# M_2_SoM_breakout_board_v0_4.net
KiCad netlist of a schematic drawn in EAGLE
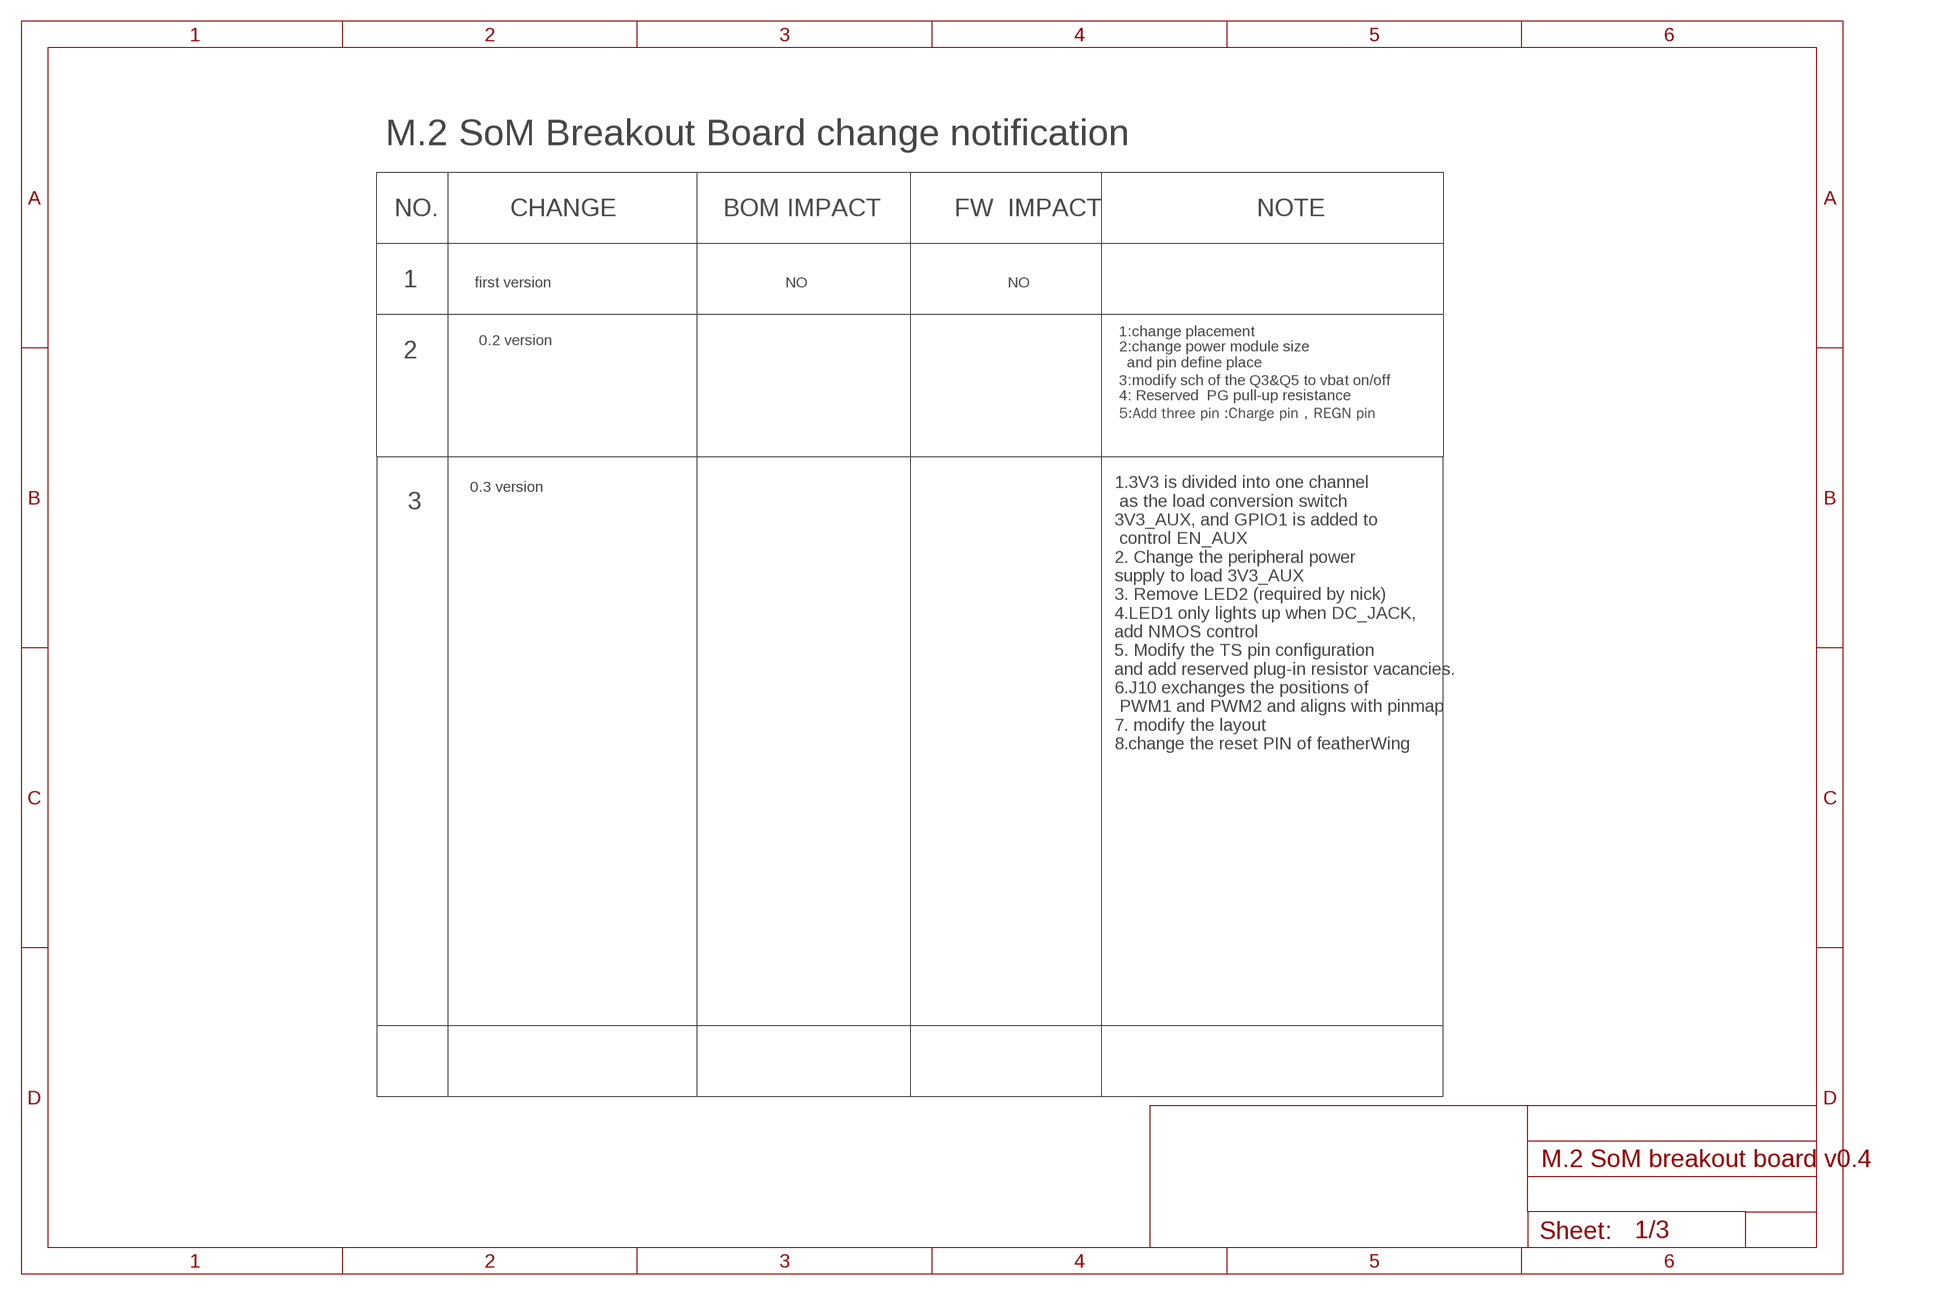
[diagram p0: schematic, sheet 1]
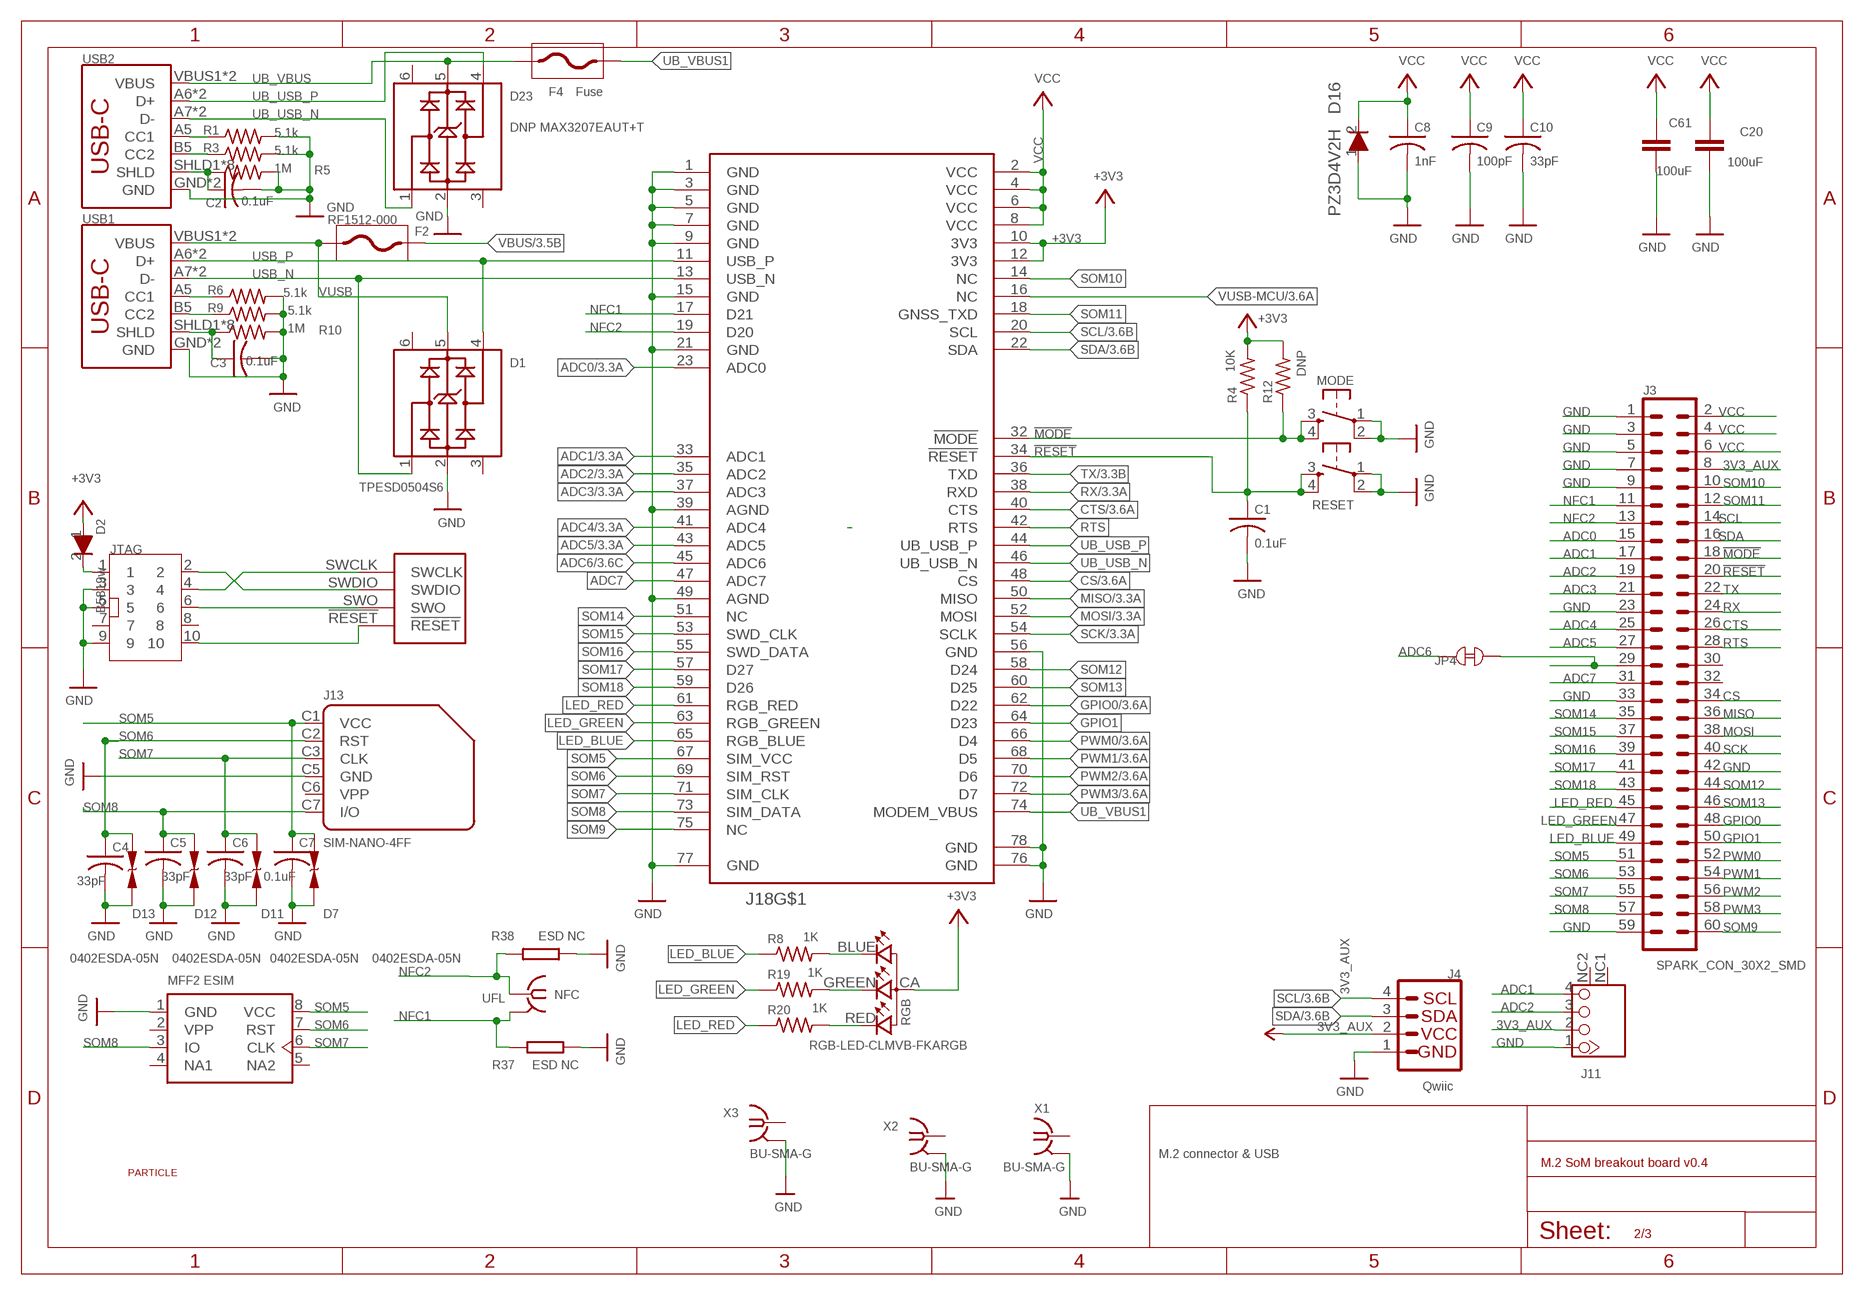
[diagram p1: schematic, sheet 2]
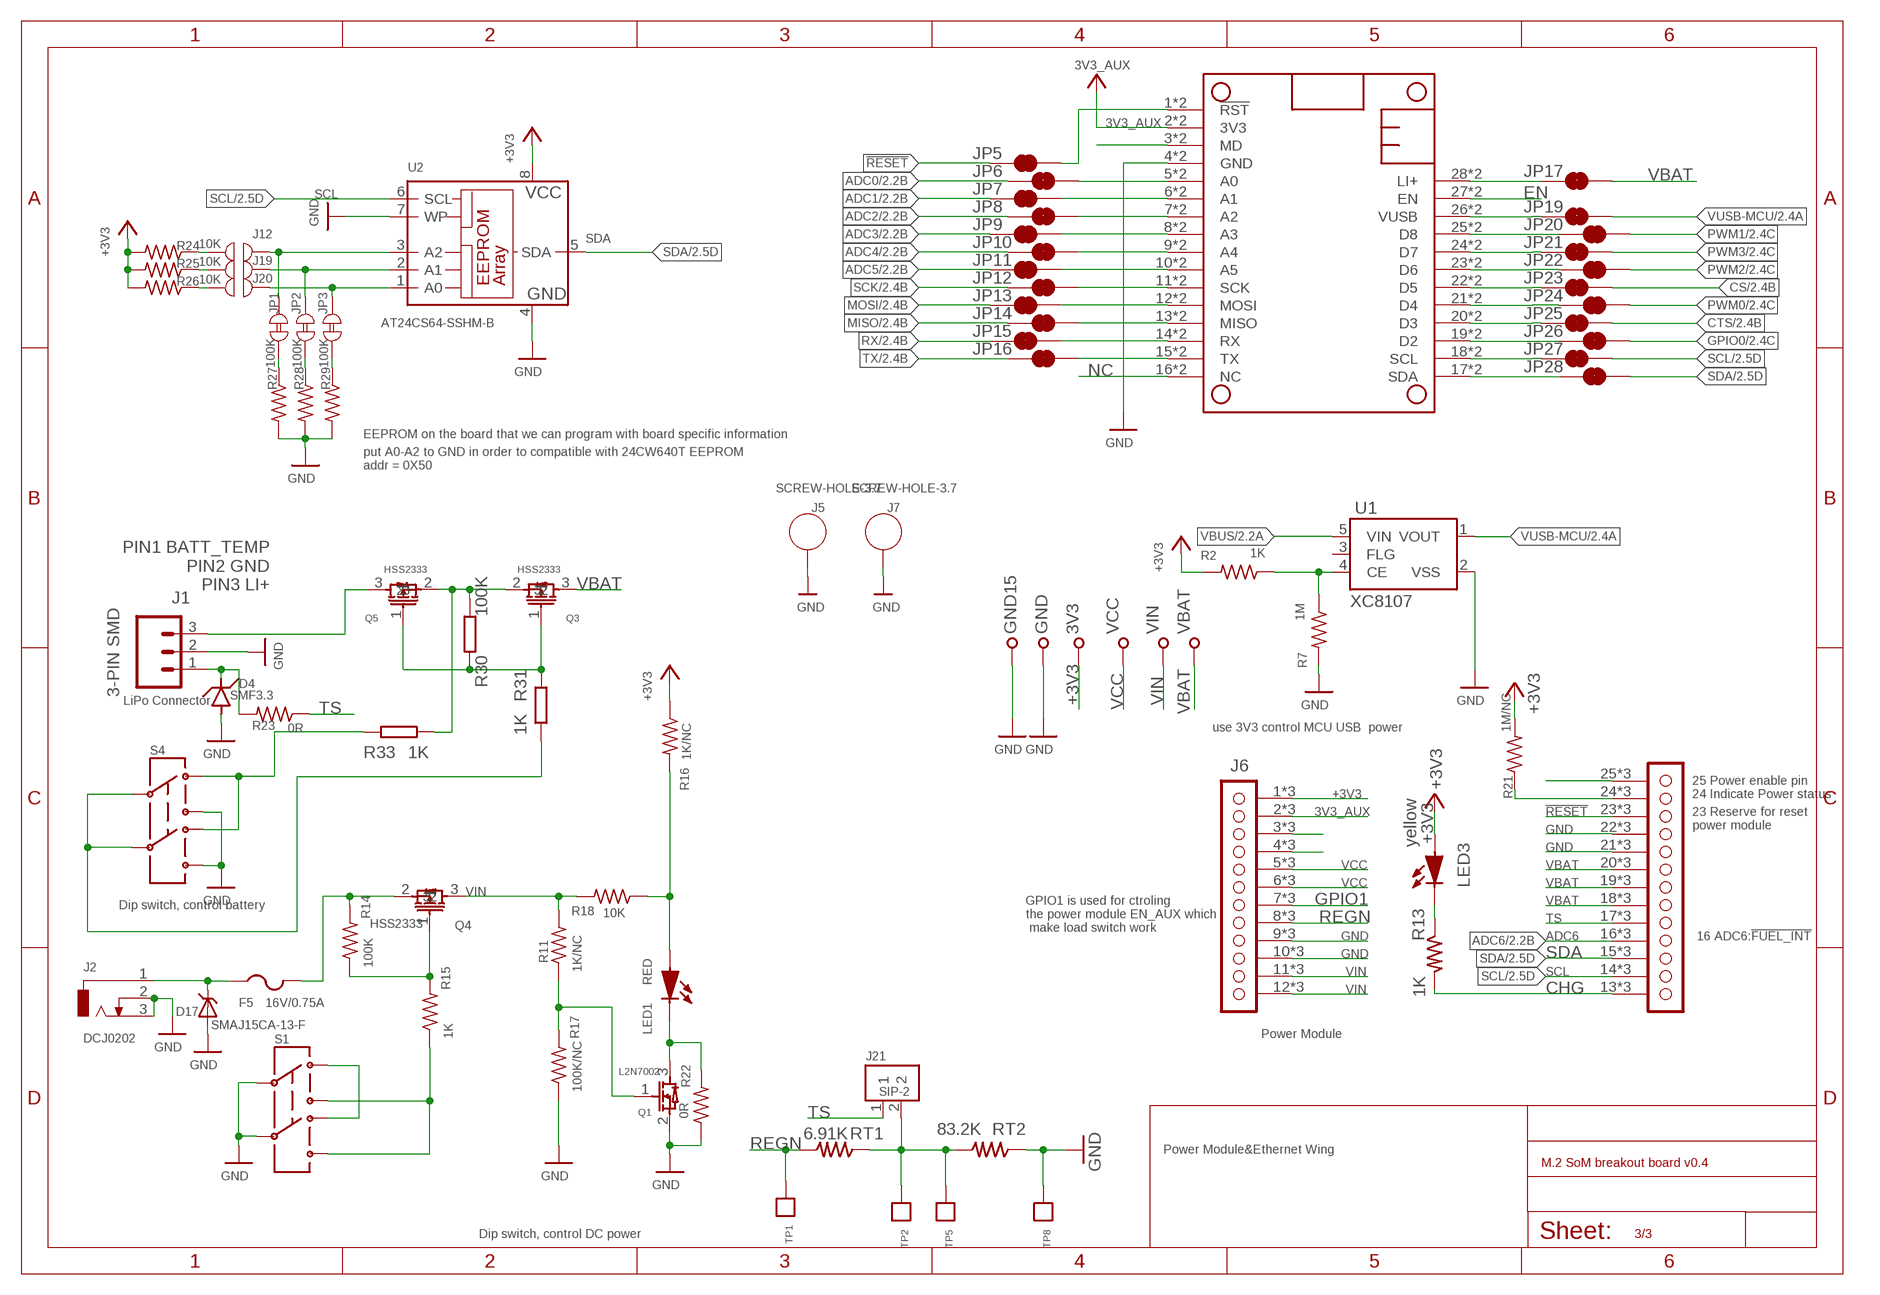
[diagram p2: schematic, sheet 3]

(export (version "E")
  (design (tool "Eeschema 10.0.6"))
  (components
    (comp (ref "3V3")
      (value "TP-S2751-46R")
      (footprint "eagle-import:S2751-46R")
      (libsource (lib "eagle-import") (part "TP-S2751-46R"))
    )
    (comp (ref "D4")
      (value "SMF3.3")
      (footprint "eagle-import:SOD-123FL")
      (libsource (lib "eagle-import") (part "TVS-DIODE-SOD123FL"))
    )
    (comp (ref "D17")
      (value "SMAJ15CA-13-F")
      (footprint "eagle-import:SMADIODE")
      (libsource (lib "eagle-import") (part "DIODE-ZENER"))
    )
    (comp (ref "F5")
      (value "16V/0.75A")
      (footprint "eagle-import:1812")
      (libsource (lib "eagle-import") (part "PTCFUSE-1812"))
    )
    (comp (ref "GND")
      (value "TP-S2751-46R")
      (footprint "eagle-import:S2751-46R")
      (libsource (lib "eagle-import") (part "TP-S2751-46R"))
    )
    (comp (ref "GND15")
      (value "TP-S2751-46R")
      (footprint "eagle-import:S2751-46R")
      (libsource (lib "eagle-import") (part "TP-S2751-46R"))
    )
    (comp (ref "J1")
      (value "3-PIN SMD")
      (footprint "eagle-import:JST-3-SMD")
      (libsource (lib "eagle-import") (part "CONN_03JST-SMD"))
    )
    (comp (ref "J2")
      (value "DCJ0202")
      (footprint "eagle-import:DCJ0202")
      (libsource (lib "eagle-import") (part "DCJ0202"))
    )
    (comp (ref "J5")
      (value "SCREW-HOLE-3.7")
      (footprint "eagle-import:SCREW-HOLE-3.7")
      (libsource (lib "eagle-import") (part "SCREW-HOLE-3.7"))
    )
    (comp (ref "J6")
      (value "M.2-SOM-BREAKOUT-BOARD-V0.2-0228_PARTICLE-SZ_PARTICLE-POWER-MODULE")
      (footprint "eagle-import:M.2-SOM-BREAKOUT-BOARD-V0.2-0228_PARTICLE-SZ_PARTICLE-POWER-MODULE")
      (libsource (lib "eagle-import") (part "M.2-SOM-BREAKOUT-BOARD-V0.2-0228_PARTICLE-SZ_PARTICLE-POWER-MODULE"))
    )
    (comp (ref "J7")
      (value "SCREW-HOLE-3.7")
      (footprint "eagle-import:SCREW-HOLE-3.7")
      (libsource (lib "eagle-import") (part "SCREW-HOLE-3.7"))
    )
    (comp (ref "J12")
      (value "TP_OPEN")
      (footprint "eagle-import:TP_OPEN")
      (libsource (lib "eagle-import") (part "TP_OPEN"))
    )
    (comp (ref "J19")
      (value "TP_OPEN")
      (footprint "eagle-import:TP_OPEN")
      (libsource (lib "eagle-import") (part "TP_OPEN"))
    )
    (comp (ref "J20")
      (value "TP_OPEN")
      (footprint "eagle-import:TP_OPEN")
      (libsource (lib "eagle-import") (part "TP_OPEN"))
    )
    (comp (ref "J21")
      (value "SIP-2")
      (footprint "eagle-import:SIP-2")
      (libsource (lib "eagle-import") (part "SIP-2"))
    )
    (comp (ref "JP1")
      (value "TP_SHORT")
      (footprint "eagle-import:TP_SHORT")
      (libsource (lib "eagle-import") (part "TP_SHORT"))
    )
    (comp (ref "JP2")
      (value "TP_SHORT")
      (footprint "eagle-import:TP_SHORT")
      (libsource (lib "eagle-import") (part "TP_SHORT"))
    )
    (comp (ref "JP3")
      (value "TP_SHORT")
      (footprint "eagle-import:TP_SHORT")
      (libsource (lib "eagle-import") (part "TP_SHORT"))
    )
    (comp (ref "JP5")
      (value "JUMPER-SMT_2_NC_TRACE_NO-SILK")
      (footprint "eagle-import:SMT-JUMPER_2_NC_TRACE_NO-SILK")
      (libsource (lib "eagle-import") (part "JUMPER-SMT_2_NC_TRACE_NO-SILK"))
    )
    (comp (ref "JP6")
      (value "JUMPER-SMT_2_NC_TRACE_NO-SILK")
      (footprint "eagle-import:SMT-JUMPER_2_NC_TRACE_NO-SILK")
      (libsource (lib "eagle-import") (part "JUMPER-SMT_2_NC_TRACE_NO-SILK"))
    )
    (comp (ref "JP7")
      (value "JUMPER-SMT_2_NC_TRACE_NO-SILK")
      (footprint "eagle-import:SMT-JUMPER_2_NC_TRACE_NO-SILK")
      (libsource (lib "eagle-import") (part "JUMPER-SMT_2_NC_TRACE_NO-SILK"))
    )
    (comp (ref "JP8")
      (value "JUMPER-SMT_2_NC_TRACE_NO-SILK")
      (footprint "eagle-import:SMT-JUMPER_2_NC_TRACE_NO-SILK")
      (libsource (lib "eagle-import") (part "JUMPER-SMT_2_NC_TRACE_NO-SILK"))
    )
    (comp (ref "JP9")
      (value "JUMPER-SMT_2_NC_TRACE_NO-SILK")
      (footprint "eagle-import:SMT-JUMPER_2_NC_TRACE_NO-SILK")
      (libsource (lib "eagle-import") (part "JUMPER-SMT_2_NC_TRACE_NO-SILK"))
    )
    (comp (ref "JP10")
      (value "JUMPER-SMT_2_NC_TRACE_NO-SILK")
      (footprint "eagle-import:SMT-JUMPER_2_NC_TRACE_NO-SILK")
      (libsource (lib "eagle-import") (part "JUMPER-SMT_2_NC_TRACE_NO-SILK"))
    )
    (comp (ref "JP11")
      (value "JUMPER-SMT_2_NC_TRACE_NO-SILK")
      (footprint "eagle-import:SMT-JUMPER_2_NC_TRACE_NO-SILK")
      (libsource (lib "eagle-import") (part "JUMPER-SMT_2_NC_TRACE_NO-SILK"))
    )
    (comp (ref "JP12")
      (value "JUMPER-SMT_2_NC_TRACE_NO-SILK")
      (footprint "eagle-import:SMT-JUMPER_2_NC_TRACE_NO-SILK")
      (libsource (lib "eagle-import") (part "JUMPER-SMT_2_NC_TRACE_NO-SILK"))
    )
    (comp (ref "JP13")
      (value "JUMPER-SMT_2_NC_TRACE_NO-SILK")
      (footprint "eagle-import:SMT-JUMPER_2_NC_TRACE_NO-SILK")
      (libsource (lib "eagle-import") (part "JUMPER-SMT_2_NC_TRACE_NO-SILK"))
    )
    (comp (ref "JP14")
      (value "JUMPER-SMT_2_NC_TRACE_NO-SILK")
      (footprint "eagle-import:SMT-JUMPER_2_NC_TRACE_NO-SILK")
      (libsource (lib "eagle-import") (part "JUMPER-SMT_2_NC_TRACE_NO-SILK"))
    )
    (comp (ref "JP15")
      (value "JUMPER-SMT_2_NC_TRACE_NO-SILK")
      (footprint "eagle-import:SMT-JUMPER_2_NC_TRACE_NO-SILK")
      (libsource (lib "eagle-import") (part "JUMPER-SMT_2_NC_TRACE_NO-SILK"))
    )
    (comp (ref "JP16")
      (value "JUMPER-SMT_2_NC_TRACE_NO-SILK")
      (footprint "eagle-import:SMT-JUMPER_2_NC_TRACE_NO-SILK")
      (libsource (lib "eagle-import") (part "JUMPER-SMT_2_NC_TRACE_NO-SILK"))
    )
    (comp (ref "JP17")
      (value "JUMPER-SMT_2_NC_TRACE_NO-SILK")
      (footprint "eagle-import:SMT-JUMPER_2_NC_TRACE_NO-SILK")
      (libsource (lib "eagle-import") (part "JUMPER-SMT_2_NC_TRACE_NO-SILK"))
    )
    (comp (ref "JP19")
      (value "JUMPER-SMT_2_NC_TRACE_NO-SILK")
      (footprint "eagle-import:SMT-JUMPER_2_NC_TRACE_NO-SILK")
      (libsource (lib "eagle-import") (part "JUMPER-SMT_2_NC_TRACE_NO-SILK"))
    )
    (comp (ref "JP20")
      (value "JUMPER-SMT_2_NC_TRACE_NO-SILK")
      (footprint "eagle-import:SMT-JUMPER_2_NC_TRACE_NO-SILK")
      (libsource (lib "eagle-import") (part "JUMPER-SMT_2_NC_TRACE_NO-SILK"))
    )
    (comp (ref "JP21")
      (value "JUMPER-SMT_2_NC_TRACE_NO-SILK")
      (footprint "eagle-import:SMT-JUMPER_2_NC_TRACE_NO-SILK")
      (libsource (lib "eagle-import") (part "JUMPER-SMT_2_NC_TRACE_NO-SILK"))
    )
    (comp (ref "JP22")
      (value "JUMPER-SMT_2_NC_TRACE_NO-SILK")
      (footprint "eagle-import:SMT-JUMPER_2_NC_TRACE_NO-SILK")
      (libsource (lib "eagle-import") (part "JUMPER-SMT_2_NC_TRACE_NO-SILK"))
    )
    (comp (ref "JP23")
      (value "JUMPER-SMT_2_NC_TRACE_NO-SILK")
      (footprint "eagle-import:SMT-JUMPER_2_NC_TRACE_NO-SILK")
      (libsource (lib "eagle-import") (part "JUMPER-SMT_2_NC_TRACE_NO-SILK"))
    )
    (comp (ref "JP24")
      (value "JUMPER-SMT_2_NC_TRACE_NO-SILK")
      (footprint "eagle-import:SMT-JUMPER_2_NC_TRACE_NO-SILK")
      (libsource (lib "eagle-import") (part "JUMPER-SMT_2_NC_TRACE_NO-SILK"))
    )
    (comp (ref "JP25")
      (value "JUMPER-SMT_2_NC_TRACE_NO-SILK")
      (footprint "eagle-import:SMT-JUMPER_2_NC_TRACE_NO-SILK")
      (libsource (lib "eagle-import") (part "JUMPER-SMT_2_NC_TRACE_NO-SILK"))
    )
    (comp (ref "JP26")
      (value "JUMPER-SMT_2_NC_TRACE_NO-SILK")
      (footprint "eagle-import:SMT-JUMPER_2_NC_TRACE_NO-SILK")
      (libsource (lib "eagle-import") (part "JUMPER-SMT_2_NC_TRACE_NO-SILK"))
    )
    (comp (ref "JP27")
      (value "JUMPER-SMT_2_NC_TRACE_NO-SILK")
      (footprint "eagle-import:SMT-JUMPER_2_NC_TRACE_NO-SILK")
      (libsource (lib "eagle-import") (part "JUMPER-SMT_2_NC_TRACE_NO-SILK"))
    )
    (comp (ref "JP28")
      (value "JUMPER-SMT_2_NC_TRACE_NO-SILK")
      (footprint "eagle-import:SMT-JUMPER_2_NC_TRACE_NO-SILK")
      (libsource (lib "eagle-import") (part "JUMPER-SMT_2_NC_TRACE_NO-SILK"))
    )
    (comp (ref "LED1")
      (value "RED")
      (footprint "eagle-import:LED0603")
      (libsource (lib "eagle-import") (part "LED"))
    )
    (comp (ref "LED3")
      (value "yellow")
      (footprint "eagle-import:LED0603")
      (libsource (lib "eagle-import") (part "LED"))
    )
    (comp (ref "MS1")
      (value "PARTICLE_MESH_SMTDUAL")
      (footprint "eagle-import:FEATHERWING_SMT2")
      (libsource (lib "eagle-import") (part "PARTICLE_MESH_SMTDUAL"))
    )
    (comp (ref "Q1")
      (value "L2N7002")
      (footprint "eagle-import:SOT323")
      (libsource (lib "eagle-import") (part "NMOSSOT323"))
    )
    (comp (ref "Q3")
      (value "HSS2333")
      (footprint "eagle-import:SOT-23")
      (libsource (lib "eagle-import") (part "PMOS"))
    )
    (comp (ref "Q4")
      (value "HSS2333")
      (footprint "eagle-import:SOT-23")
      (libsource (lib "eagle-import") (part "PMOS"))
    )
    (comp (ref "Q5")
      (value "HSS2333")
      (footprint "eagle-import:SOT-23")
      (libsource (lib "eagle-import") (part "PMOS"))
    )
    (comp (ref "R2")
      (value "1K")
      (footprint "eagle-import:R0402_B")
      (libsource (lib "eagle-import") (part "R-US_"))
    )
    (comp (ref "R7")
      (value "1M")
      (footprint "eagle-import:R0402_B")
      (libsource (lib "eagle-import") (part "R-US_"))
    )
    (comp (ref "R11")
      (value "1K/NC")
      (footprint "eagle-import:R0402_B")
      (libsource (lib "eagle-import") (part "R-US_"))
    )
    (comp (ref "R13")
      (value "1K")
      (footprint "eagle-import:R-0402S")
      (libsource (lib "eagle-import") (part "particle SZ_RES0402S"))
    )
    (comp (ref "R14")
      (value "100K")
      (footprint "eagle-import:R0402_B")
      (libsource (lib "eagle-import") (part "R-US_"))
    )
    (comp (ref "R15")
      (value "1K")
      (footprint "eagle-import:R0402_B")
      (libsource (lib "eagle-import") (part "R-US_"))
    )
    (comp (ref "R16")
      (value "1K/NC")
      (footprint "eagle-import:R0402_B")
      (libsource (lib "eagle-import") (part "R-US_"))
    )
    (comp (ref "R17")
      (value "100K/NC")
      (footprint "eagle-import:R0402_B")
      (libsource (lib "eagle-import") (part "R-US_"))
    )
    (comp (ref "R18")
      (value "10K")
      (footprint "eagle-import:R0402_B")
      (libsource (lib "eagle-import") (part "R-US_"))
    )
    (comp (ref "R21")
      (value "1M/NC")
      (footprint "eagle-import:R0402_B")
      (libsource (lib "eagle-import") (part "R-US_"))
    )
    (comp (ref "R22")
      (value "0R")
      (footprint "eagle-import:R0402_B")
      (libsource (lib "eagle-import") (part "R-US_"))
    )
    (comp (ref "R23")
      (value "0R")
      (footprint "eagle-import:R0402_B")
      (libsource (lib "eagle-import") (part "R-US_"))
    )
    (comp (ref "R24")
      (value "10K")
      (footprint "eagle-import:R0402_B")
      (libsource (lib "eagle-import") (part "R-US_"))
    )
    (comp (ref "R25")
      (value "10K")
      (footprint "eagle-import:R0402_B")
      (libsource (lib "eagle-import") (part "R-US_"))
    )
    (comp (ref "R26")
      (value "10K")
      (footprint "eagle-import:R0402_B")
      (libsource (lib "eagle-import") (part "R-US_"))
    )
    (comp (ref "R27")
      (value "100K")
      (footprint "eagle-import:R0402_B")
      (libsource (lib "eagle-import") (part "R-US_"))
    )
    (comp (ref "R28")
      (value "100K")
      (footprint "eagle-import:R0402_B")
      (libsource (lib "eagle-import") (part "R-US_"))
    )
    (comp (ref "R29")
      (value "100K")
      (footprint "eagle-import:R0402_B")
      (libsource (lib "eagle-import") (part "R-US_"))
    )
    (comp (ref "R30")
      (value "100K")
      (footprint "eagle-import:R0603")
      (libsource (lib "eagle-import") (part "RESR0603"))
    )
    (comp (ref "R31")
      (value "1K")
      (footprint "eagle-import:R-0402S")
      (libsource (lib "eagle-import") (part "RES0402S"))
    )
    (comp (ref "R33")
      (value "1K")
      (footprint "eagle-import:R-0402S")
      (libsource (lib "eagle-import") (part "RES0402S"))
    )
    (comp (ref "RT1")
      (value "6.91K")
      (footprint "eagle-import:R-0603A")
      (libsource (lib "eagle-import") (part "RESR0603A"))
    )
    (comp (ref "RT2")
      (value "83.2K")
      (footprint "eagle-import:R-0603A")
      (libsource (lib "eagle-import") (part "RESR0603A"))
    )
    (comp (ref "S1")
      (value "SWITCH-DPDT")
      (footprint "eagle-import:SWITCH-2.5X3.2-6")
      (libsource (lib "eagle-import") (part "SWITCH-DPDT"))
    )
    (comp (ref "S4")
      (value "SWITCH-DPDT")
      (footprint "eagle-import:SWITCH-2.5X3.2-6")
      (libsource (lib "eagle-import") (part "SWITCH-DPDT"))
    )
    (comp (ref "TP1")
      (value "TPTPEB")
      (footprint "eagle-import:TPEB")
      (libsource (lib "eagle-import") (part "TPTPEB"))
    )
    (comp (ref "TP2")
      (value "TPTPEB")
      (footprint "eagle-import:TPEB")
      (libsource (lib "eagle-import") (part "TPTPEB"))
    )
    (comp (ref "TP5")
      (value "TPTPEB")
      (footprint "eagle-import:TPEB")
      (libsource (lib "eagle-import") (part "TPTPEB"))
    )
    (comp (ref "TP8")
      (value "TPTPEB")
      (footprint "eagle-import:TPEB")
      (libsource (lib "eagle-import") (part "TPTPEB"))
    )
    (comp (ref "U1")
      (value "XC8107")
      (footprint "eagle-import:SOT25")
      (libsource (lib "eagle-import") (part "XC8107SOT25"))
    )
    (comp (ref "U2")
      (value "AT24CS64-SSHM-B")
      (footprint "eagle-import:SO-08")
      (fields (field (name "MF") "MICROCHIP") (field (name "MPN") "24AA01/SN"))
      (libsource (lib "eagle-import") (part "24SNAA01"))
    )
    (comp (ref "VBAT")
      (value "TP-S2751-46R")
      (footprint "eagle-import:S2751-46R")
      (libsource (lib "eagle-import") (part "TP-S2751-46R"))
    )
    (comp (ref "VCC")
      (value "TP-S2751-46R")
      (footprint "eagle-import:S2751-46R")
      (libsource (lib "eagle-import") (part "TP-S2751-46R"))
    )
    (comp (ref "VIN")
      (value "TP-S2751-46R")
      (footprint "eagle-import:S2751-46R")
      (libsource (lib "eagle-import") (part "TP-S2751-46R"))
    )
    (comp (ref "C1")
      (value "0.1uF")
      (footprint "eagle-import:C0402_B")
      (libsource (lib "eagle-import") (part "C-US"))
    )
    (comp (ref "C2")
      (value "0.1uF")
      (footprint "eagle-import:C0402_B")
      (libsource (lib "eagle-import") (part "C-US"))
    )
    (comp (ref "C3")
      (value "0.1uF")
      (footprint "eagle-import:C0402_B")
      (libsource (lib "eagle-import") (part "C-US"))
    )
    (comp (ref "C4")
      (value "33pF")
      (footprint "eagle-import:C0402_B")
      (libsource (lib "eagle-import") (part "C-US"))
    )
    (comp (ref "C5")
      (value "33pF")
      (footprint "eagle-import:C0402_B")
      (libsource (lib "eagle-import") (part "C-US"))
    )
    (comp (ref "C6")
      (value "33pF")
      (footprint "eagle-import:C0402_B")
      (libsource (lib "eagle-import") (part "C-US"))
    )
    (comp (ref "C7")
      (value "0.1uF")
      (footprint "eagle-import:C0402_B")
      (libsource (lib "eagle-import") (part "C-US"))
    )
    (comp (ref "C8")
      (value "1nF")
      (footprint "eagle-import:C0402_B")
      (libsource (lib "eagle-import") (part "C-US"))
    )
    (comp (ref "C9")
      (value "100pF")
      (footprint "eagle-import:C0402_B")
      (libsource (lib "eagle-import") (part "C-US"))
    )
    (comp (ref "C10")
      (value "33pF")
      (footprint "eagle-import:C0402_B")
      (libsource (lib "eagle-import") (part "C-US"))
    )
    (comp (ref "C20")
      (value "100uF")
      (footprint "eagle-import:C1206K")
      (libsource (lib "eagle-import") (part "C-EUC1206K"))
    )
    (comp (ref "C61")
      (value "100uF")
      (footprint "eagle-import:C1206K")
      (libsource (lib "eagle-import") (part "C-EUC1206K"))
    )
    (comp (ref "D1")
      (value "TPESD0504S6")
      (footprint "eagle-import:SOT23-6")
      (fields (field (name "MFG") "MAXIM") (field (name "MPN") "MAX3207EAUT+T"))
      (libsource (lib "eagle-import") (part "MAX3207EAUT+T"))
    )
    (comp (ref "D2")
      (value "B5819w")
      (footprint "eagle-import:SOD-123")
      (libsource (lib "eagle-import") (part "DIODESOD123"))
    )
    (comp (ref "D7")
      (value "0402ESDA-05N")
      (footprint "eagle-import:C0402")
      (libsource (lib "eagle-import") (part "ESD"))
    )
    (comp (ref "D11")
      (value "0402ESDA-05N")
      (footprint "eagle-import:C0402")
      (libsource (lib "eagle-import") (part "ESD"))
    )
    (comp (ref "D12")
      (value "0402ESDA-05N")
      (footprint "eagle-import:C0402")
      (libsource (lib "eagle-import") (part "ESD"))
    )
    (comp (ref "D13")
      (value "0402ESDA-05N")
      (footprint "eagle-import:C0402")
      (libsource (lib "eagle-import") (part "ESD"))
    )
    (comp (ref "D16")
      (value "PZ3D4V2H")
      (footprint "eagle-import:SOD-323")
      (libsource (lib "eagle-import") (part "DIODESOD323"))
    )
    (comp (ref "D23")
      (value "DNP MAX3207EAUT+T")
      (footprint "eagle-import:SOT23-6")
      (fields (field (name "MFG") "MAXIM") (field (name "MPN") "MAX3207EAUT+T"))
      (libsource (lib "eagle-import") (part "MAX3207EAUT+T"))
    )
    (comp (ref "F2")
      (value "RF1512-000")
      (footprint "eagle-import:F0805")
      (libsource (lib "eagle-import") (part "FUSE"))
    )
    (comp (ref "F4")
      (value "Fuse")
      (footprint "eagle-import:F0805")
      (libsource (lib "eagle-import") (part "FUSE"))
    )
    (comp (ref "J3")
      (value "SPARK_CON_30X2_SMD")
      (footprint "eagle-import:SPARK_CON_30X2_SMD")
      (libsource (lib "eagle-import") (part "SPARK_CON_30X2_SMD"))
    )
    (comp (ref "J4")
      (value "QWIIC_CONNECTORJS-1MM")
      (footprint "eagle-import:1X04_1MM_RA")
      (libsource (lib "eagle-import") (part "QWIIC_CONNECTORJS-1MM"))
    )
    (comp (ref "J11")
      (value "WAFER-HY2.0-4PWB")
      (footprint "eagle-import:M.2-SOM-BREAKOUT-BOARD-V0.2-0228_WAFER-HY2.0-4PWB")
      (libsource (lib "eagle-import") (part "M.2-SOM-BREAKOUT-BOARD-V0.2-0228_WAFER-HY2.0-4PWB"))
    )
    (comp (ref "J13")
      (value "SIM-NANO-4FF")
      (footprint "eagle-import:GCT-SIM8100")
      (libsource (lib "eagle-import") (part "SIM-NANO-4FF"))
    )
    (comp (ref "J18")
      (value "PARTICLE-STUDIOS_M_SERIES_M.2KEY")
      (footprint "eagle-import:PARTICLE-STUDIOS_PARTICLE_M.2EKEY_3.65MM_DRILL")
      (libsource (lib "eagle-import") (part "PARTICLE-STUDIOS_M_SERIES_M.2KEY"))
    )
    (comp (ref "JP4")
      (value "TP_SHORT")
      (footprint "eagle-import:TP_SHORT")
      (libsource (lib "eagle-import") (part "TP_SHORT"))
    )
    (comp (ref "JTAG")
      (value "CONN5X2")
      (footprint "eagle-import:CONN5X2_1.27")
      (fields (field (name "MFG") "KAWEEI") (field (name "MPN") "P6014A-M2GC-030-10"))
      (libsource (lib "eagle-import") (part "CONN5X2"))
    )
    (comp (ref "MODE")
      (value "TAC_SWITCHSMD")
      (footprint "eagle-import:TACTILE_SWITCH_SMD")
      (fields (field (name "MFG") "HAOYU") (field (name "MPN") "TS-1185A-025C"))
      (libsource (lib "eagle-import") (part "TAC_SWITCHSMD"))
    )
    (comp (ref "NFC")
      (value "UFL")
      (footprint "eagle-import:IPEX-20279-001E")
      (libsource (lib "eagle-import") (part "IPEX-20279-001E"))
    )
    (comp (ref "R1")
      (value "5.1k")
      (footprint "eagle-import:R0402_B")
      (libsource (lib "eagle-import") (part "R-US_"))
    )
    (comp (ref "R3")
      (value "5.1k")
      (footprint "eagle-import:R0402_B")
      (libsource (lib "eagle-import") (part "R-US_"))
    )
    (comp (ref "R4")
      (value "10K")
      (footprint "eagle-import:R0402_B")
      (libsource (lib "eagle-import") (part "R-US_"))
    )
    (comp (ref "R5")
      (value "1M")
      (footprint "eagle-import:R0402_B")
      (libsource (lib "eagle-import") (part "R-US_"))
    )
    (comp (ref "R6")
      (value "5.1k")
      (footprint "eagle-import:R0402_B")
      (libsource (lib "eagle-import") (part "R-US_"))
    )
    (comp (ref "R8")
      (value "1K")
      (footprint "eagle-import:R0402_B")
      (libsource (lib "eagle-import") (part "R-US_"))
    )
    (comp (ref "R9")
      (value "5.1k")
      (footprint "eagle-import:R0402_B")
      (libsource (lib "eagle-import") (part "R-US_"))
    )
    (comp (ref "R10")
      (value "1M")
      (footprint "eagle-import:R0402_B")
      (libsource (lib "eagle-import") (part "R-US_"))
    )
    (comp (ref "R12")
      (value "DNP")
      (footprint "eagle-import:R0402_B")
      (libsource (lib "eagle-import") (part "R-US_"))
    )
    (comp (ref "R19")
      (value "1K")
      (footprint "eagle-import:R0402_B")
      (libsource (lib "eagle-import") (part "R-US_"))
    )
    (comp (ref "R20")
      (value "1K")
      (footprint "eagle-import:R0402_B")
      (libsource (lib "eagle-import") (part "R-US_"))
    )
    (comp (ref "R37")
      (value "ESD NC")
      (footprint "eagle-import:R-0402S")
      (libsource (lib "eagle-import") (part "RES0402S"))
    )
    (comp (ref "R38")
      (value "ESD NC")
      (footprint "eagle-import:R-0402S")
      (libsource (lib "eagle-import") (part "RES0402S"))
    )
    (comp (ref "RESET")
      (value "TAC_SWITCHSMD")
      (footprint "eagle-import:TACTILE_SWITCH_SMD")
      (fields (field (name "MFG") "HAOYU") (field (name "MPN") "TS-1185A-025C"))
      (libsource (lib "eagle-import") (part "TAC_SWITCHSMD"))
    )
    (comp (ref "RGB")
      (value "RGB-LED-CLMVB-FKARGB")
      (footprint "eagle-import:PLCC4-2MM-RGB")
      (libsource (lib "eagle-import") (part "RGB-LED-CLMVB-FKARGB"))
    )
    (comp (ref "U$6")
      (value "PARTICLE-LOGO")
      (footprint "eagle-import:PARTICLE-LOGO")
      (libsource (lib "eagle-import") (part "PARTICLE-LOGO"))
    )
    (comp (ref "U7")
      (value "NC")
      (footprint "eagle-import:MFF2")
      (libsource (lib "eagle-import") (part "ESIMSON8"))
    )
    (comp (ref "USB1")
      (value "USB_C16PIN")
      (footprint "eagle-import:USB-C-16P")
      (libsource (lib "eagle-import") (part "USB_C16PIN"))
    )
    (comp (ref "USB2")
      (value "USB_C16PIN")
      (footprint "eagle-import:USB-C-16P")
      (libsource (lib "eagle-import") (part "USB_C16PIN"))
    )
    (comp (ref "X1")
      (value "BU-SMA-G")
      (footprint "eagle-import:BU-SMA-G")
      (libsource (lib "eagle-import") (part "BU-SMA-G"))
    )
    (comp (ref "X2")
      (value "BU-SMA-G")
      (footprint "eagle-import:BU-SMA-G")
      (libsource (lib "eagle-import") (part "BU-SMA-G"))
    )
    (comp (ref "X3")
      (value "BU-SMA-G")
      (footprint "eagle-import:BU-SMA-G")
      (libsource (lib "eagle-import") (part "BU-SMA-G"))
    )
  )
  (nets
    (net (code "1") (name "+3V3") (class "Default")
      (node (ref "3V3") (pin "1") (pinfunction "TP_1") (pintype "bidirectional"))
      (node (ref "D2") (pin "1") (pinfunction "P$1_1") (pintype "bidirectional"))
      (node (ref "J18") (pin "10") (pinfunction "3V3_10") (pintype "power_in"))
      (node (ref "J18") (pin "12") (pinfunction "3V3_12") (pintype "power_in"))
      (node (ref "J6") (pin "1") (pinfunction "3V3_1") (pintype "passive"))
      (node (ref "J6") (pin "@1") (pinfunction "3V3_@1") (pintype "passive"))
      (node (ref "J6") (pin "P$1") (pinfunction "3V3_P$1") (pintype "passive"))
      (node (ref "LED3") (pin "1") (pinfunction "A_1") (pintype "bidirectional"))
      (node (ref "R12") (pin "2") (pinfunction "2_2") (pintype "passive"))
      (node (ref "R16") (pin "1") (pinfunction "1_1") (pintype "passive"))
      (node (ref "R2") (pin "2") (pinfunction "2_2") (pintype "passive"))
      (node (ref "R21") (pin "2") (pinfunction "2_2") (pintype "passive"))
      (node (ref "R24") (pin "2") (pinfunction "2_2") (pintype "passive"))
      (node (ref "R25") (pin "2") (pinfunction "2_2") (pintype "passive"))
      (node (ref "R26") (pin "2") (pinfunction "2_2") (pintype "passive"))
      (node (ref "R4") (pin "2") (pinfunction "2_2") (pintype "passive"))
      (node (ref "RGB") (pin "CA") (pinfunction "1_CA") (pintype "passive"))
      (node (ref "U2") (pin "8") (pinfunction "VCC_8") (pintype "power_in"))
    )
    (net (code "2") (name "3V3_AUX") (class "Default")
      (node (ref "J11") (pin "2") (pinfunction "2_2") (pintype "bidirectional"))
      (node (ref "J3") (pin "8") (pinfunction "8_8") (pintype "passive"))
      (node (ref "J4") (pin "2") (pinfunction "2_2") (pintype "power_in"))
      (node (ref "J6") (pin "2") (pinfunction "3V3_2") (pintype "passive"))
      (node (ref "J6") (pin "@2") (pinfunction "3V3_@2") (pintype "passive"))
      (node (ref "J6") (pin "P$2") (pinfunction "3V3_P$2") (pintype "passive"))
      (node (ref "MS1") (pin "2") (pinfunction "3V3_2") (pintype "power_in"))
      (node (ref "MS1") (pin "2'") (pinfunction "3V3_2'") (pintype "power_in"))
    )
    (net (code "3") (name "ADC0") (class "Default")
      (node (ref "J18") (pin "23") (pinfunction "ADC0_23") (pintype "bidirectional"))
      (node (ref "J3") (pin "15") (pinfunction "15_15") (pintype "passive"))
      (node (ref "JP6") (pin "1") (pinfunction "1_1") (pintype "passive"))
    )
    (net (code "4") (name "ADC1") (class "Default")
      (node (ref "J11") (pin "4") (pinfunction "4_4") (pintype "bidirectional"))
      (node (ref "J18") (pin "33") (pinfunction "ADC1_33") (pintype "bidirectional"))
      (node (ref "J3") (pin "17") (pinfunction "17_17") (pintype "passive"))
      (node (ref "JP7") (pin "1") (pinfunction "1_1") (pintype "passive"))
    )
    (net (code "5") (name "ADC2") (class "Default")
      (node (ref "J11") (pin "3") (pinfunction "3_3") (pintype "bidirectional"))
      (node (ref "J18") (pin "35") (pinfunction "ADC2_35") (pintype "bidirectional"))
      (node (ref "J3") (pin "19") (pinfunction "19_19") (pintype "passive"))
      (node (ref "JP8") (pin "1") (pinfunction "1_1") (pintype "passive"))
    )
    (net (code "6") (name "ADC3") (class "Default")
      (node (ref "J18") (pin "37") (pinfunction "ADC3_37") (pintype "bidirectional"))
      (node (ref "J3") (pin "21") (pinfunction "21_21") (pintype "passive"))
      (node (ref "JP9") (pin "1") (pinfunction "1_1") (pintype "passive"))
    )
    (net (code "7") (name "ADC4") (class "Default")
      (node (ref "J18") (pin "41") (pinfunction "ADC4_41") (pintype "bidirectional"))
      (node (ref "J3") (pin "25") (pinfunction "25_25") (pintype "passive"))
      (node (ref "JP10") (pin "1") (pinfunction "1_1") (pintype "passive"))
    )
    (net (code "8") (name "ADC5") (class "Default")
      (node (ref "J18") (pin "43") (pinfunction "ADC5_43") (pintype "bidirectional"))
      (node (ref "J3") (pin "27") (pinfunction "27_27") (pintype "passive"))
      (node (ref "JP11") (pin "1") (pinfunction "1_1") (pintype "passive"))
    )
    (net (code "9") (name "ADC6") (class "Default")
      (node (ref "J18") (pin "45") (pinfunction "ADC6_45") (pintype "bidirectional"))
      (node (ref "J6") (pin "16") (pinfunction "~{FUEL-INT}_16") (pintype "passive"))
      (node (ref "J6") (pin "@16") (pinfunction "~{FUEL-INT}_@16") (pintype "passive"))
      (node (ref "J6") (pin "P$16") (pinfunction "~{FUEL-INT}_P$16") (pintype "passive"))
      (node (ref "JP4") (pin "2") (pinfunction "2_2") (pintype "bidirectional"))
    )
    (net (code "10") (name "ADC7") (class "Default")
      (node (ref "J18") (pin "47") (pinfunction "ADC7_47") (pintype "bidirectional"))
      (node (ref "J3") (pin "31") (pinfunction "31_31") (pintype "passive"))
    )
    (net (code "11") (name "CHG") (class "Default")
      (node (ref "J6") (pin "13") (pinfunction "CHG_13") (pintype "passive"))
      (node (ref "J6") (pin "@13") (pinfunction "CHG_@13") (pintype "passive"))
      (node (ref "J6") (pin "P$13") (pinfunction "CHG_P$13") (pintype "passive"))
      (node (ref "R13") (pin "2") (pinfunction "2_2") (pintype "bidirectional"))
    )
    (net (code "12") (name "CS") (class "Default")
      (node (ref "J18") (pin "48") (pinfunction "CS_48") (pintype "bidirectional"))
      (node (ref "J3") (pin "34") (pinfunction "34_34") (pintype "passive"))
      (node (ref "JP23") (pin "2") (pinfunction "2_2") (pintype "passive"))
    )
    (net (code "13") (name "CTS") (class "Default")
      (node (ref "J18") (pin "40") (pinfunction "CTS_40") (pintype "bidirectional"))
      (node (ref "J3") (pin "26") (pinfunction "26_26") (pintype "passive"))
      (node (ref "JP25") (pin "2") (pinfunction "2_2") (pintype "passive"))
    )
    (net (code "14") (name "EN") (class "Default")
      (node (ref "MS1") (pin "27") (pinfunction "EN_27") (pintype "passive"))
      (node (ref "MS1") (pin "27'") (pinfunction "EN_27'") (pintype "passive"))
    )
    (net (code "15") (name "GND") (class "Default")
      (node (ref "C1") (pin "2") (pinfunction "2_2") (pintype "passive"))
      (node (ref "C10") (pin "2") (pinfunction "2_2") (pintype "passive"))
      (node (ref "C2") (pin "2") (pinfunction "2_2") (pintype "passive"))
      (node (ref "C20") (pin "2") (pinfunction "2_2") (pintype "passive"))
      (node (ref "C3") (pin "2") (pinfunction "2_2") (pintype "passive"))
      (node (ref "C4") (pin "2") (pinfunction "2_2") (pintype "passive"))
      (node (ref "C5") (pin "2") (pinfunction "2_2") (pintype "passive"))
      (node (ref "C6") (pin "2") (pinfunction "2_2") (pintype "passive"))
      (node (ref "C61") (pin "2") (pinfunction "2_2") (pintype "passive"))
      (node (ref "C7") (pin "2") (pinfunction "2_2") (pintype "passive"))
      (node (ref "C8") (pin "2") (pinfunction "2_2") (pintype "passive"))
      (node (ref "C9") (pin "2") (pinfunction "2_2") (pintype "passive"))
      (node (ref "D1") (pin "2") (pinfunction "2_2") (pintype "bidirectional"))
      (node (ref "D11") (pin "1") (pinfunction "1_1") (pintype "bidirectional"))
      (node (ref "D12") (pin "1") (pinfunction "1_1") (pintype "bidirectional"))
      (node (ref "D13") (pin "1") (pinfunction "1_1") (pintype "bidirectional"))
      (node (ref "D16") (pin "1") (pinfunction "P$1_1") (pintype "bidirectional"))
      (node (ref "D17") (pin "A") (pinfunction "A_A") (pintype "passive"))
      (node (ref "D23") (pin "2") (pinfunction "2_2") (pintype "bidirectional"))
      (node (ref "D4") (pin "A") (pinfunction "A_A") (pintype "passive"))
      (node (ref "D7") (pin "1") (pinfunction "1_1") (pintype "bidirectional"))
      (node (ref "GND") (pin "1") (pinfunction "TP_1") (pintype "bidirectional"))
      (node (ref "GND15") (pin "1") (pinfunction "TP_1") (pintype "bidirectional"))
      (node (ref "J1") (pin "2") (pinfunction "2_2") (pintype "passive"))
      (node (ref "J11") (pin "1") (pinfunction "1_1") (pintype "bidirectional"))
      (node (ref "J13") (pin "C5") (pinfunction "GND_C5") (pintype "passive"))
      (node (ref "J18") (pin "1") (pinfunction "GND_1") (pintype "power_in"))
      (node (ref "J18") (pin "15") (pinfunction "GND_15") (pintype "power_in"))
      (node (ref "J18") (pin "21") (pinfunction "GND_21") (pintype "power_in"))
      (node (ref "J18") (pin "3") (pinfunction "GND_3") (pintype "power_in"))
      (node (ref "J18") (pin "39") (pinfunction "AGND_39") (pintype "power_in"))
      (node (ref "J18") (pin "49") (pinfunction "AGND_49") (pintype "power_in"))
      (node (ref "J18") (pin "5") (pinfunction "GND_5") (pintype "power_in"))
      (node (ref "J18") (pin "56") (pinfunction "GND_56") (pintype "power_in"))
      (node (ref "J18") (pin "7") (pinfunction "GND_7") (pintype "power_in"))
      (node (ref "J18") (pin "76") (pinfunction "GND_76") (pintype "power_in"))
      (node (ref "J18") (pin "77") (pinfunction "GND_77") (pintype "power_in"))
      (node (ref "J18") (pin "78") (pinfunction "GND_78") (pintype "power_in"))
      (node (ref "J18") (pin "9") (pinfunction "GND_9") (pintype "power_in"))
      (node (ref "J2") (pin "2") (pinfunction "2_2") (pintype "passive"))
      (node (ref "J2") (pin "3") (pinfunction "3_3") (pintype "passive"))
      (node (ref "J3") (pin "1") (pinfunction "1_1") (pintype "passive"))
      (node (ref "J3") (pin "23") (pinfunction "23_23") (pintype "passive"))
      (node (ref "J3") (pin "3") (pinfunction "3_3") (pintype "passive"))
      (node (ref "J3") (pin "33") (pinfunction "33_33") (pintype "passive"))
      (node (ref "J3") (pin "42") (pinfunction "42_42") (pintype "passive"))
      (node (ref "J3") (pin "5") (pinfunction "5_5") (pintype "passive"))
      (node (ref "J3") (pin "59") (pinfunction "59_59") (pintype "passive"))
      (node (ref "J3") (pin "7") (pinfunction "7_7") (pintype "passive"))
      (node (ref "J3") (pin "9") (pinfunction "9_9") (pintype "passive"))
      (node (ref "J4") (pin "1") (pinfunction "1_1") (pintype "power_in"))
      (node (ref "J5") (pin "P$1") (pinfunction "GND_P$1") (pintype "bidirectional"))
      (node (ref "J6") (pin "10") (pinfunction "GND_10") (pintype "passive"))
      (node (ref "J6") (pin "21") (pinfunction "GND_21") (pintype "passive"))
      (node (ref "J6") (pin "22") (pinfunction "GND_22") (pintype "passive"))
      (node (ref "J6") (pin "9") (pinfunction "GND_9") (pintype "passive"))
      (node (ref "J6") (pin "@10") (pinfunction "GND_@10") (pintype "passive"))
      (node (ref "J6") (pin "@21") (pinfunction "GND_@21") (pintype "passive"))
      (node (ref "J6") (pin "@22") (pinfunction "GND_@22") (pintype "passive"))
      (node (ref "J6") (pin "@9") (pinfunction "GND_@9") (pintype "passive"))
      (node (ref "J6") (pin "P$10") (pinfunction "GND_P$10") (pintype "passive"))
      (node (ref "J6") (pin "P$21") (pinfunction "GND_P$21") (pintype "passive"))
      (node (ref "J6") (pin "P$22") (pinfunction "GND_P$22") (pintype "passive"))
      (node (ref "J6") (pin "P$9") (pinfunction "GND_P$9") (pintype "passive"))
      (node (ref "J7") (pin "P$1") (pinfunction "GND_P$1") (pintype "bidirectional"))
      (node (ref "JTAG") (pin "3") (pinfunction "3_3") (pintype "bidirectional"))
      (node (ref "JTAG") (pin "5") (pinfunction "5_5") (pintype "bidirectional"))
      (node (ref "JTAG") (pin "9") (pinfunction "9_9") (pintype "bidirectional"))
      (node (ref "MODE") (pin "1") (pinfunction "1_1") (pintype "passive"))
      (node (ref "MODE") (pin "2") (pinfunction "2_2") (pintype "passive"))
      (node (ref "MS1") (pin "4") (pinfunction "GND_4") (pintype "power_in"))
      (node (ref "MS1") (pin "4'") (pinfunction "GND_4'") (pintype "power_in"))
      (node (ref "Q1") (pin "2") (pinfunction "2_2") (pintype "bidirectional"))
      (node (ref "R1") (pin "2") (pinfunction "2_2") (pintype "passive"))
      (node (ref "R10") (pin "2") (pinfunction "2_2") (pintype "passive"))
      (node (ref "R17") (pin "1") (pinfunction "1_1") (pintype "passive"))
      (node (ref "R22") (pin "1") (pinfunction "1_1") (pintype "passive"))
      (node (ref "R27") (pin "2") (pinfunction "2_2") (pintype "passive"))
      (node (ref "R28") (pin "2") (pinfunction "2_2") (pintype "passive"))
      (node (ref "R29") (pin "2") (pinfunction "2_2") (pintype "passive"))
      (node (ref "R3") (pin "2") (pinfunction "2_2") (pintype "passive"))
      (node (ref "R37") (pin "2") (pinfunction "2_2") (pintype "bidirectional"))
      (node (ref "R38") (pin "1") (pinfunction "1_1") (pintype "bidirectional"))
      (node (ref "R5") (pin "2") (pinfunction "2_2") (pintype "passive"))
      (node (ref "R6") (pin "2") (pinfunction "2_2") (pintype "passive"))
      (node (ref "R7") (pin "2") (pinfunction "2_2") (pintype "passive"))
      (node (ref "R9") (pin "2") (pinfunction "2_2") (pintype "passive"))
      (node (ref "RESET") (pin "1") (pinfunction "1_1") (pintype "passive"))
      (node (ref "RESET") (pin "2") (pinfunction "2_2") (pintype "passive"))
      (node (ref "RT2") (pin "1") (pinfunction "1_1") (pintype "bidirectional"))
      (node (ref "S1") (pin "2") (pinfunction "2_2") (pintype "bidirectional"))
      (node (ref "S1") (pin "5") (pinfunction "5_5") (pintype "bidirectional"))
      (node (ref "S4") (pin "3") (pinfunction "3_3") (pintype "bidirectional"))
      (node (ref "S4") (pin "6") (pinfunction "6_6") (pintype "bidirectional"))
      (node (ref "TP8") (pin "1") (pinfunction "1_1") (pintype "bidirectional"))
      (node (ref "U1") (pin "2") (pinfunction "VSS_2") (pintype "power_in"))
      (node (ref "U2") (pin "4") (pinfunction "GND_4") (pintype "power_in"))
      (node (ref "U2") (pin "7") (pinfunction "WP_7") (pintype "input"))
      (node (ref "U7") (pin "1") (pinfunction "GND_1") (pintype "power_in"))
      (node (ref "USB1") (pin "GND") (pinfunction "GND_GND") (pintype "bidirectional"))
      (node (ref "USB1") (pin "GND2") (pinfunction "GND_GND2") (pintype "bidirectional"))
      (node (ref "USB2") (pin "GND") (pinfunction "GND_GND") (pintype "bidirectional"))
      (node (ref "USB2") (pin "GND2") (pinfunction "GND_GND2") (pintype "bidirectional"))
      (node (ref "X1") (pin "2") (pinfunction "2_2") (pintype "passive"))
      (node (ref "X1") (pin "3") (pinfunction "2_3") (pintype "passive"))
      (node (ref "X1") (pin "4") (pinfunction "2_4") (pintype "passive"))
      (node (ref "X1") (pin "5") (pinfunction "2_5") (pintype "passive"))
      (node (ref "X2") (pin "2") (pinfunction "2_2") (pintype "passive"))
      (node (ref "X2") (pin "3") (pinfunction "2_3") (pintype "passive"))
      (node (ref "X2") (pin "4") (pinfunction "2_4") (pintype "passive"))
      (node (ref "X2") (pin "5") (pinfunction "2_5") (pintype "passive"))
      (node (ref "X3") (pin "2") (pinfunction "2_2") (pintype "passive"))
      (node (ref "X3") (pin "3") (pinfunction "2_3") (pintype "passive"))
      (node (ref "X3") (pin "4") (pinfunction "2_4") (pintype "passive"))
      (node (ref "X3") (pin "5") (pinfunction "2_5") (pintype "passive"))
    )
    (net (code "16") (name "GPIO0") (class "Default")
      (node (ref "J18") (pin "62") (pinfunction "D22_62") (pintype "bidirectional"))
      (node (ref "J3") (pin "48") (pinfunction "48_48") (pintype "passive"))
      (node (ref "JP26") (pin "2") (pinfunction "2_2") (pintype "passive"))
    )
    (net (code "17") (name "GPIO1") (class "Default")
      (node (ref "J18") (pin "64") (pinfunction "D23_64") (pintype "bidirectional"))
      (node (ref "J3") (pin "50") (pinfunction "50_50") (pintype "passive"))
      (node (ref "J6") (pin "7") (pinfunction "REGN_7") (pintype "passive"))
      (node (ref "J6") (pin "@7") (pinfunction "REGN_@7") (pintype "passive"))
      (node (ref "J6") (pin "P$7") (pinfunction "REGN_P$7") (pintype "passive"))
    )
    (net (code "18") (name "LED_BLUE") (class "Default")
      (node (ref "J18") (pin "65") (pinfunction "RGB_BLUE_65") (pintype "bidirectional"))
      (node (ref "J3") (pin "49") (pinfunction "49_49") (pintype "passive"))
      (node (ref "R8") (pin "1") (pinfunction "1_1") (pintype "passive"))
    )
    (net (code "19") (name "LED_GREEN") (class "Default")
      (node (ref "J18") (pin "63") (pinfunction "RGB_GREEN_63") (pintype "bidirectional"))
      (node (ref "J3") (pin "47") (pinfunction "47_47") (pintype "passive"))
      (node (ref "R19") (pin "1") (pinfunction "1_1") (pintype "passive"))
    )
    (net (code "20") (name "LED_RED") (class "Default")
      (node (ref "J18") (pin "61") (pinfunction "RGB_RED_61") (pintype "bidirectional"))
      (node (ref "J3") (pin "45") (pinfunction "45_45") (pintype "passive"))
      (node (ref "R20") (pin "1") (pinfunction "1_1") (pintype "passive"))
    )
    (net (code "21") (name "MISO") (class "Default")
      (node (ref "J18") (pin "50") (pinfunction "MISO_50") (pintype "bidirectional"))
      (node (ref "J3") (pin "36") (pinfunction "36_36") (pintype "passive"))
      (node (ref "JP14") (pin "1") (pinfunction "1_1") (pintype "passive"))
    )
    (net (code "22") (name "MOSI") (class "Default")
      (node (ref "J18") (pin "52") (pinfunction "MOSI_52") (pintype "bidirectional"))
      (node (ref "J3") (pin "38") (pinfunction "38_38") (pintype "passive"))
      (node (ref "JP13") (pin "1") (pinfunction "1_1") (pintype "passive"))
    )
    (net (code "23") (name "NC") (class "Default")
      (node (ref "MS1") (pin "16") (pinfunction "NC_16") (pintype "passive"))
      (node (ref "MS1") (pin "16'") (pinfunction "NC_16'") (pintype "passive"))
    )
    (net (code "24") (name "NFC1") (class "Default")
      (node (ref "J18") (pin "17") (pinfunction "D21_17") (pintype "bidirectional"))
      (node (ref "J3") (pin "11") (pinfunction "11_11") (pintype "passive"))
      (node (ref "NFC") (pin "2@1") (pinfunction "GND_2@1") (pintype "passive"))
      (node (ref "NFC") (pin "2@2") (pinfunction "GND_2@2") (pintype "passive"))
      (node (ref "R37") (pin "1") (pinfunction "1_1") (pintype "bidirectional"))
    )
    (net (code "25") (name "NFC2") (class "Default")
      (node (ref "J18") (pin "19") (pinfunction "D20_19") (pintype "bidirectional"))
      (node (ref "J3") (pin "13") (pinfunction "13_13") (pintype "passive"))
      (node (ref "NFC") (pin "1") (pinfunction "1_1") (pintype "passive"))
      (node (ref "R38") (pin "2") (pinfunction "2_2") (pintype "bidirectional"))
    )
    (net (code "26") (name "Net-(C2-Pad1)") (class "Default")
      (node (ref "C2") (pin "1") (pinfunction "1_1") (pintype "passive"))
      (node (ref "R5") (pin "1") (pinfunction "1_1") (pintype "passive"))
      (node (ref "USB2") (pin "SHLD1") (pinfunction "SHLD_SHLD1") (pintype "bidirectional"))
      (node (ref "USB2") (pin "SHLD2") (pinfunction "SHLD_SHLD2") (pintype "bidirectional"))
      (node (ref "USB2") (pin "SHLD3") (pinfunction "SHLD_SHLD3") (pintype "bidirectional"))
      (node (ref "USB2") (pin "SHLD4") (pinfunction "SHLD_SHLD4") (pintype "bidirectional"))
      (node (ref "USB2") (pin "SHLD5") (pinfunction "SHLD_SHLD5") (pintype "bidirectional"))
      (node (ref "USB2") (pin "SHLD6") (pinfunction "SHLD_SHLD6") (pintype "bidirectional"))
      (node (ref "USB2") (pin "SHLD7") (pinfunction "SHLD_SHLD7") (pintype "bidirectional"))
      (node (ref "USB2") (pin "SHLD8") (pinfunction "SHLD_SHLD8") (pintype "bidirectional"))
    )
    (net (code "27") (name "Net-(C3-Pad1)") (class "Default")
      (node (ref "C3") (pin "1") (pinfunction "1_1") (pintype "passive"))
      (node (ref "R10") (pin "1") (pinfunction "1_1") (pintype "passive"))
      (node (ref "USB1") (pin "SHLD1") (pinfunction "SHLD_SHLD1") (pintype "bidirectional"))
      (node (ref "USB1") (pin "SHLD2") (pinfunction "SHLD_SHLD2") (pintype "bidirectional"))
      (node (ref "USB1") (pin "SHLD3") (pinfunction "SHLD_SHLD3") (pintype "bidirectional"))
      (node (ref "USB1") (pin "SHLD4") (pinfunction "SHLD_SHLD4") (pintype "bidirectional"))
      (node (ref "USB1") (pin "SHLD5") (pinfunction "SHLD_SHLD5") (pintype "bidirectional"))
      (node (ref "USB1") (pin "SHLD6") (pinfunction "SHLD_SHLD6") (pintype "bidirectional"))
      (node (ref "USB1") (pin "SHLD7") (pinfunction "SHLD_SHLD7") (pintype "bidirectional"))
      (node (ref "USB1") (pin "SHLD8") (pinfunction "SHLD_SHLD8") (pintype "bidirectional"))
    )
    (net (code "28") (name "Net-(D2-P$2)") (class "Default")
      (node (ref "D2") (pin "2") (pinfunction "P$2_2") (pintype "bidirectional"))
      (node (ref "JTAG") (pin "1") (pinfunction "1_1") (pintype "bidirectional"))
    )
    (net (code "29") (name "Net-(D4-PadC)") (class "Default")
      (node (ref "D4") (pin "C") (pinfunction "C_C") (pintype "passive"))
      (node (ref "J1") (pin "1") (pinfunction "1_1") (pintype "passive"))
      (node (ref "R23") (pin "2") (pinfunction "2_2") (pintype "passive"))
    )
    (net (code "30") (name "Net-(D17-PadC)") (class "Default")
      (node (ref "D17") (pin "C") (pinfunction "C_C") (pintype "passive"))
      (node (ref "F5") (pin "1") (pinfunction "1_1") (pintype "passive"))
      (node (ref "J2") (pin "1") (pinfunction "1_1") (pintype "passive"))
    )
    (net (code "31") (name "Net-(F5-Pad2)") (class "Default")
      (node (ref "F5") (pin "2") (pinfunction "2_2") (pintype "passive"))
      (node (ref "Q4") (pin "2") (pinfunction "2_2") (pintype "bidirectional"))
      (node (ref "R14") (pin "2") (pinfunction "2_2") (pintype "passive"))
    )
    (net (code "32") (name "Net-(J1-Pad3)") (class "Default")
      (node (ref "J1") (pin "3") (pinfunction "3_3") (pintype "passive"))
      (node (ref "Q5") (pin "3") (pinfunction "3_3") (pintype "bidirectional"))
    )
    (net (code "33") (name "Net-(J3-Pad29)") (class "Default")
      (node (ref "J3") (pin "29") (pinfunction "29_29") (pintype "passive"))
      (node (ref "JP4") (pin "1") (pinfunction "1_1") (pintype "bidirectional"))
    )
    (net (code "34") (name "Net-(J6-5DC-Pad3)") (class "Default")
      (node (ref "J6") (pin "3") (pinfunction "5DC_3") (pintype "passive"))
      (node (ref "J6") (pin "@3") (pinfunction "5DC_@3") (pintype "passive"))
      (node (ref "J6") (pin "P$3") (pinfunction "5DC_P$3") (pintype "passive"))
    )
    (net (code "35") (name "Net-(J6-5DC-Pad4)") (class "Default")
      (node (ref "J6") (pin "4") (pinfunction "5DC_4") (pintype "passive"))
      (node (ref "J6") (pin "@4") (pinfunction "5DC_@4") (pintype "passive"))
      (node (ref "J6") (pin "P$4") (pinfunction "5DC_P$4") (pintype "passive"))
    )
    (net (code "36") (name "Net-(J6-ENABLE-Pad25)") (class "Default")
      (node (ref "J6") (pin "25") (pinfunction "ENABLE_25") (pintype "passive"))
      (node (ref "J6") (pin "@25") (pinfunction "ENABLE_@25") (pintype "passive"))
      (node (ref "J6") (pin "P$25") (pinfunction "ENABLE_P$25") (pintype "passive"))
    )
    (net (code "37") (name "Net-(J6-PG-Pad24)") (class "Default")
      (node (ref "J6") (pin "24") (pinfunction "PG_24") (pintype "passive"))
      (node (ref "J6") (pin "@24") (pinfunction "PG_@24") (pintype "passive"))
      (node (ref "J6") (pin "P$24") (pinfunction "PG_P$24") (pintype "passive"))
      (node (ref "R21") (pin "1") (pinfunction "1_1") (pintype "passive"))
    )
    (net (code "38") (name "Net-(J12-Pad1)") (class "Default")
      (node (ref "J12") (pin "1") (pinfunction "1_1") (pintype "bidirectional"))
      (node (ref "R24") (pin "1") (pinfunction "1_1") (pintype "passive"))
    )
    (net (code "39") (name "Net-(J18-PadSWCLK)") (class "Default")
      (node (ref "J18") (pin "SWCLK") (pinfunction "SWCLK_SWCLK") (pintype "power_in"))
      (node (ref "JTAG") (pin "4") (pinfunction "4_4") (pintype "bidirectional"))
    )
    (net (code "40") (name "Net-(J18-PadSWDIO)") (class "Default")
      (node (ref "J18") (pin "SWDIO") (pinfunction "SWDIO_SWDIO") (pintype "power_in"))
      (node (ref "JTAG") (pin "2") (pinfunction "2_2") (pintype "bidirectional"))
    )
    (net (code "41") (name "Net-(J18-PadSWO)") (class "Default")
      (node (ref "J18") (pin "SWO") (pinfunction "SWO_SWO") (pintype "power_in"))
      (node (ref "JTAG") (pin "6") (pinfunction "6_6") (pintype "bidirectional"))
    )
    (net (code "42") (name "Net-(J19-Pad1)") (class "Default")
      (node (ref "J19") (pin "1") (pinfunction "1_1") (pintype "bidirectional"))
      (node (ref "R25") (pin "1") (pinfunction "1_1") (pintype "passive"))
    )
    (net (code "43") (name "Net-(J20-Pad1)") (class "Default")
      (node (ref "J20") (pin "1") (pinfunction "1_1") (pintype "bidirectional"))
      (node (ref "R26") (pin "1") (pinfunction "1_1") (pintype "passive"))
    )
    (net (code "44") (name "Net-(J21-Pad2)") (class "Default")
      (node (ref "J21") (pin "2") (pinfunction "2_2") (pintype "bidirectional"))
      (node (ref "RT1") (pin "1") (pinfunction "1_1") (pintype "bidirectional"))
      (node (ref "RT2") (pin "2") (pinfunction "2_2") (pintype "bidirectional"))
      (node (ref "TP2") (pin "1") (pinfunction "1_1") (pintype "bidirectional"))
      (node (ref "TP5") (pin "1") (pinfunction "1_1") (pintype "bidirectional"))
    )
    (net (code "45") (name "Net-(JP1-Pad1)") (class "Default")
      (node (ref "JP1") (pin "1") (pinfunction "1_1") (pintype "bidirectional"))
      (node (ref "R27") (pin "1") (pinfunction "1_1") (pintype "passive"))
    )
    (net (code "46") (name "Net-(JP2-Pad1)") (class "Default")
      (node (ref "JP2") (pin "1") (pinfunction "1_1") (pintype "bidirectional"))
      (node (ref "R28") (pin "1") (pinfunction "1_1") (pintype "passive"))
    )
    (net (code "47") (name "Net-(JP3-Pad1)") (class "Default")
      (node (ref "JP3") (pin "1") (pinfunction "1_1") (pintype "bidirectional"))
      (node (ref "R29") (pin "1") (pinfunction "1_1") (pintype "passive"))
    )
    (net (code "48") (name "Net-(JP5-Pad2)") (class "Default")
      (node (ref "JP5") (pin "2") (pinfunction "2_2") (pintype "passive"))
      (node (ref "MS1") (pin "1") (pinfunction "~{RST}_1") (pintype "input"))
      (node (ref "MS1") (pin "1'") (pinfunction "~{RST}_1'") (pintype "input"))
    )
    (net (code "49") (name "Net-(JP6-Pad2)") (class "Default")
      (node (ref "JP6") (pin "2") (pinfunction "2_2") (pintype "passive"))
      (node (ref "MS1") (pin "5") (pinfunction "A0_5") (pintype "bidirectional"))
      (node (ref "MS1") (pin "5'") (pinfunction "A0_5'") (pintype "bidirectional"))
    )
    (net (code "50") (name "Net-(JP7-Pad2)") (class "Default")
      (node (ref "JP7") (pin "2") (pinfunction "2_2") (pintype "passive"))
      (node (ref "MS1") (pin "6") (pinfunction "A1_6") (pintype "bidirectional"))
      (node (ref "MS1") (pin "6'") (pinfunction "A1_6'") (pintype "bidirectional"))
    )
    (net (code "51") (name "Net-(JP8-Pad2)") (class "Default")
      (node (ref "JP8") (pin "2") (pinfunction "2_2") (pintype "passive"))
      (node (ref "MS1") (pin "7") (pinfunction "A2_7") (pintype "bidirectional"))
      (node (ref "MS1") (pin "7'") (pinfunction "A2_7'") (pintype "bidirectional"))
    )
    (net (code "52") (name "Net-(JP9-Pad2)") (class "Default")
      (node (ref "JP9") (pin "2") (pinfunction "2_2") (pintype "passive"))
      (node (ref "MS1") (pin "8") (pinfunction "A3_8") (pintype "bidirectional"))
      (node (ref "MS1") (pin "8'") (pinfunction "A3_8'") (pintype "bidirectional"))
    )
    (net (code "53") (name "Net-(JP10-Pad2)") (class "Default")
      (node (ref "JP10") (pin "2") (pinfunction "2_2") (pintype "passive"))
      (node (ref "MS1") (pin "9") (pinfunction "A4_9") (pintype "bidirectional"))
      (node (ref "MS1") (pin "9'") (pinfunction "A4_9'") (pintype "bidirectional"))
    )
    (net (code "54") (name "Net-(JP11-Pad2)") (class "Default")
      (node (ref "JP11") (pin "2") (pinfunction "2_2") (pintype "passive"))
      (node (ref "MS1") (pin "10") (pinfunction "A5_10") (pintype "bidirectional"))
      (node (ref "MS1") (pin "10'") (pinfunction "A5_10'") (pintype "bidirectional"))
    )
    (net (code "55") (name "Net-(JP12-Pad2)") (class "Default")
      (node (ref "JP12") (pin "2") (pinfunction "2_2") (pintype "passive"))
      (node (ref "MS1") (pin "11") (pinfunction "SCK_11") (pintype "bidirectional"))
      (node (ref "MS1") (pin "11'") (pinfunction "SCK_11'") (pintype "bidirectional"))
    )
    (net (code "56") (name "Net-(JP13-Pad2)") (class "Default")
      (node (ref "JP13") (pin "2") (pinfunction "2_2") (pintype "passive"))
      (node (ref "MS1") (pin "12") (pinfunction "MOSI_12") (pintype "bidirectional"))
      (node (ref "MS1") (pin "12'") (pinfunction "MOSI_12'") (pintype "bidirectional"))
    )
    (net (code "57") (name "Net-(JP14-Pad2)") (class "Default")
      (node (ref "JP14") (pin "2") (pinfunction "2_2") (pintype "passive"))
      (node (ref "MS1") (pin "13") (pinfunction "MISO_13") (pintype "bidirectional"))
      (node (ref "MS1") (pin "13'") (pinfunction "MISO_13'") (pintype "bidirectional"))
    )
    (net (code "58") (name "Net-(JP15-Pad2)") (class "Default")
      (node (ref "JP15") (pin "2") (pinfunction "2_2") (pintype "passive"))
      (node (ref "MS1") (pin "14") (pinfunction "RX_14") (pintype "bidirectional"))
      (node (ref "MS1") (pin "14'") (pinfunction "RX_14'") (pintype "bidirectional"))
    )
    (net (code "59") (name "Net-(JP16-Pad2)") (class "Default")
      (node (ref "JP16") (pin "2") (pinfunction "2_2") (pintype "passive"))
      (node (ref "MS1") (pin "15") (pinfunction "TX_15") (pintype "bidirectional"))
      (node (ref "MS1") (pin "15'") (pinfunction "TX_15'") (pintype "bidirectional"))
    )
    (net (code "60") (name "Net-(JP17-Pad1)") (class "Default")
      (node (ref "JP17") (pin "1") (pinfunction "1_1") (pintype "passive"))
      (node (ref "MS1") (pin "28") (pinfunction "LI+_28") (pintype "power_in"))
      (node (ref "MS1") (pin "28'") (pinfunction "LI+_28'") (pintype "power_in"))
    )
    (net (code "61") (name "Net-(JP19-Pad1)") (class "Default")
      (node (ref "JP19") (pin "1") (pinfunction "1_1") (pintype "passive"))
      (node (ref "MS1") (pin "26") (pinfunction "VUSB_26") (pintype "power_in"))
      (node (ref "MS1") (pin "26'") (pinfunction "VUSB_26'") (pintype "power_in"))
    )
    (net (code "62") (name "Net-(JP20-Pad1)") (class "Default")
      (node (ref "JP20") (pin "1") (pinfunction "1_1") (pintype "passive"))
      (node (ref "MS1") (pin "25") (pinfunction "D8_25") (pintype "bidirectional"))
      (node (ref "MS1") (pin "25'") (pinfunction "D8_25'") (pintype "bidirectional"))
    )
    (net (code "63") (name "Net-(JP21-Pad1)") (class "Default")
      (node (ref "JP21") (pin "1") (pinfunction "1_1") (pintype "passive"))
      (node (ref "MS1") (pin "24") (pinfunction "D7_24") (pintype "bidirectional"))
      (node (ref "MS1") (pin "24'") (pinfunction "D7_24'") (pintype "bidirectional"))
    )
    (net (code "64") (name "Net-(JP22-Pad1)") (class "Default")
      (node (ref "JP22") (pin "1") (pinfunction "1_1") (pintype "passive"))
      (node (ref "MS1") (pin "23") (pinfunction "D6_23") (pintype "bidirectional"))
      (node (ref "MS1") (pin "23'") (pinfunction "D6_23'") (pintype "bidirectional"))
    )
    (net (code "65") (name "Net-(JP23-Pad1)") (class "Default")
      (node (ref "JP23") (pin "1") (pinfunction "1_1") (pintype "passive"))
      (node (ref "MS1") (pin "22") (pinfunction "D5_22") (pintype "bidirectional"))
      (node (ref "MS1") (pin "22'") (pinfunction "D5_22'") (pintype "bidirectional"))
    )
    (net (code "66") (name "Net-(JP24-Pad1)") (class "Default")
      (node (ref "JP24") (pin "1") (pinfunction "1_1") (pintype "passive"))
      (node (ref "MS1") (pin "21") (pinfunction "D4_21") (pintype "bidirectional"))
      (node (ref "MS1") (pin "21'") (pinfunction "D4_21'") (pintype "bidirectional"))
    )
    (net (code "67") (name "Net-(JP25-Pad1)") (class "Default")
      (node (ref "JP25") (pin "1") (pinfunction "1_1") (pintype "passive"))
      (node (ref "MS1") (pin "20") (pinfunction "D3_20") (pintype "bidirectional"))
      (node (ref "MS1") (pin "20'") (pinfunction "D3_20'") (pintype "bidirectional"))
    )
    (net (code "68") (name "Net-(JP26-Pad1)") (class "Default")
      (node (ref "JP26") (pin "1") (pinfunction "1_1") (pintype "passive"))
      (node (ref "MS1") (pin "19") (pinfunction "D2_19") (pintype "bidirectional"))
      (node (ref "MS1") (pin "19'") (pinfunction "D2_19'") (pintype "bidirectional"))
    )
    (net (code "69") (name "Net-(JP27-Pad1)") (class "Default")
      (node (ref "JP27") (pin "1") (pinfunction "1_1") (pintype "passive"))
      (node (ref "MS1") (pin "18") (pinfunction "SCL_18") (pintype "bidirectional"))
      (node (ref "MS1") (pin "18'") (pinfunction "SCL_18'") (pintype "bidirectional"))
    )
    (net (code "70") (name "Net-(JP28-Pad1)") (class "Default")
      (node (ref "JP28") (pin "1") (pinfunction "1_1") (pintype "passive"))
      (node (ref "MS1") (pin "17") (pinfunction "SDA_17") (pintype "bidirectional"))
      (node (ref "MS1") (pin "17'") (pinfunction "SDA_17'") (pintype "bidirectional"))
    )
    (net (code "71") (name "Net-(LED1-A)") (class "Default")
      (node (ref "LED1") (pin "1") (pinfunction "A_1") (pintype "bidirectional"))
      (node (ref "R16") (pin "2") (pinfunction "2_2") (pintype "passive"))
      (node (ref "R18") (pin "1") (pinfunction "1_1") (pintype "passive"))
    )
    (net (code "72") (name "Net-(LED1-K)") (class "Default")
      (node (ref "LED1") (pin "2") (pinfunction "K_2") (pintype "bidirectional"))
      (node (ref "Q1") (pin "3") (pinfunction "3_3") (pintype "bidirectional"))
      (node (ref "R22") (pin "2") (pinfunction "2_2") (pintype "passive"))
    )
    (net (code "73") (name "Net-(LED3-K)") (class "Default")
      (node (ref "LED3") (pin "2") (pinfunction "K_2") (pintype "bidirectional"))
      (node (ref "R13") (pin "1") (pinfunction "1_1") (pintype "bidirectional"))
    )
    (net (code "74") (name "Net-(MS1-MD-Pad3')") (class "Default")
      (node (ref "MS1") (pin "3") (pinfunction "MD_3") (pintype "bidirectional"))
      (node (ref "MS1") (pin "3'") (pinfunction "MD_3'") (pintype "bidirectional"))
    )
    (net (code "75") (name "Net-(Q1-Pad1)") (class "Default")
      (node (ref "Q1") (pin "1") (pinfunction "1_1") (pintype "bidirectional"))
      (node (ref "R11") (pin "1") (pinfunction "1_1") (pintype "passive"))
      (node (ref "R17") (pin "2") (pinfunction "2_2") (pintype "passive"))
    )
    (net (code "76") (name "Net-(Q3-Pad1)") (class "Default")
      (node (ref "Q3") (pin "1") (pinfunction "1_1") (pintype "bidirectional"))
      (node (ref "Q5") (pin "1") (pinfunction "1_1") (pintype "bidirectional"))
      (node (ref "R30") (pin "1") (pinfunction "1_1") (pintype "bidirectional"))
      (node (ref "R31") (pin "1") (pinfunction "1_1") (pintype "bidirectional"))
    )
    (net (code "77") (name "Net-(Q3-Pad2)") (class "Default")
      (node (ref "Q3") (pin "2") (pinfunction "2_2") (pintype "bidirectional"))
      (node (ref "Q5") (pin "2") (pinfunction "2_2") (pintype "bidirectional"))
      (node (ref "R30") (pin "2") (pinfunction "2_2") (pintype "bidirectional"))
      (node (ref "R33") (pin "2") (pinfunction "2_2") (pintype "bidirectional"))
    )
    (net (code "78") (name "Net-(Q4-Pad1)") (class "Default")
      (node (ref "Q4") (pin "1") (pinfunction "1_1") (pintype "bidirectional"))
      (node (ref "R14") (pin "1") (pinfunction "1_1") (pintype "passive"))
      (node (ref "R15") (pin "2") (pinfunction "2_2") (pintype "passive"))
    )
    (net (code "79") (name "Net-(R15-Pad1)") (class "Default")
      (node (ref "R15") (pin "1") (pinfunction "1_1") (pintype "passive"))
      (node (ref "S1") (pin "3") (pinfunction "3_3") (pintype "bidirectional"))
      (node (ref "S1") (pin "6") (pinfunction "6_6") (pintype "bidirectional"))
    )
    (net (code "80") (name "Net-(R31-Pad2)") (class "Default")
      (node (ref "R31") (pin "2") (pinfunction "2_2") (pintype "bidirectional"))
      (node (ref "S4") (pin "2") (pinfunction "2_2") (pintype "bidirectional"))
      (node (ref "S4") (pin "5") (pinfunction "5_5") (pintype "bidirectional"))
    )
    (net (code "81") (name "Net-(R33-Pad1)") (class "Default")
      (node (ref "R33") (pin "1") (pinfunction "1_1") (pintype "bidirectional"))
      (node (ref "S4") (pin "1") (pinfunction "1_1") (pintype "bidirectional"))
      (node (ref "S4") (pin "4") (pinfunction "4_4") (pintype "bidirectional"))
    )
    (net (code "82") (name "Net-(RGB-2)") (class "Default")
      (node (ref "R8") (pin "2") (pinfunction "2_2") (pintype "passive"))
      (node (ref "RGB") (pin "BLUE") (pinfunction "2_BLUE") (pintype "passive"))
    )
    (net (code "83") (name "Net-(RGB-3)") (class "Default")
      (node (ref "R19") (pin "2") (pinfunction "2_2") (pintype "passive"))
      (node (ref "RGB") (pin "GREEN") (pinfunction "3_GREEN") (pintype "passive"))
    )
    (net (code "84") (name "Net-(RGB-4)") (class "Default")
      (node (ref "R20") (pin "2") (pinfunction "2_2") (pintype "passive"))
      (node (ref "RGB") (pin "RED") (pinfunction "4_RED") (pintype "passive"))
    )
    (net (code "85") (name "Net-(S1-Pad1)") (class "Default")
      (node (ref "S1") (pin "1") (pinfunction "1_1") (pintype "bidirectional"))
      (node (ref "S1") (pin "4") (pinfunction "4_4") (pintype "bidirectional"))
    )
    (net (code "86") (name "Net-(U1-CE)") (class "Default")
      (node (ref "R2") (pin "1") (pinfunction "1_1") (pintype "passive"))
      (node (ref "R7") (pin "1") (pinfunction "1_1") (pintype "passive"))
      (node (ref "U1") (pin "4") (pinfunction "CE_4") (pintype "bidirectional"))
    )
    (net (code "87") (name "Net-(U2-A0)") (class "Default")
      (node (ref "J20") (pin "2") (pinfunction "2_2") (pintype "bidirectional"))
      (node (ref "JP3") (pin "2") (pinfunction "2_2") (pintype "bidirectional"))
      (node (ref "U2") (pin "1") (pinfunction "A0_1") (pintype "input"))
    )
    (net (code "88") (name "Net-(U2-A1)") (class "Default")
      (node (ref "J19") (pin "2") (pinfunction "2_2") (pintype "bidirectional"))
      (node (ref "JP2") (pin "2") (pinfunction "2_2") (pintype "bidirectional"))
      (node (ref "U2") (pin "2") (pinfunction "A1_2") (pintype "input"))
    )
    (net (code "89") (name "Net-(U2-A2)") (class "Default")
      (node (ref "J12") (pin "2") (pinfunction "2_2") (pintype "bidirectional"))
      (node (ref "JP1") (pin "2") (pinfunction "2_2") (pintype "bidirectional"))
      (node (ref "U2") (pin "3") (pinfunction "A2_3") (pintype "input"))
    )
    (net (code "90") (name "Net-(USB1-CC1)") (class "Default")
      (node (ref "R6") (pin "1") (pinfunction "1_1") (pintype "passive"))
      (node (ref "USB1") (pin "A5") (pinfunction "CC1_A5") (pintype "bidirectional"))
    )
    (net (code "91") (name "Net-(USB1-CC2)") (class "Default")
      (node (ref "R9") (pin "1") (pinfunction "1_1") (pintype "passive"))
      (node (ref "USB1") (pin "B5") (pinfunction "CC2_B5") (pintype "bidirectional"))
    )
    (net (code "92") (name "Net-(USB2-CC1)") (class "Default")
      (node (ref "R1") (pin "1") (pinfunction "1_1") (pintype "passive"))
      (node (ref "USB2") (pin "A5") (pinfunction "CC1_A5") (pintype "bidirectional"))
    )
    (net (code "93") (name "Net-(USB2-CC2)") (class "Default")
      (node (ref "R3") (pin "1") (pinfunction "1_1") (pintype "passive"))
      (node (ref "USB2") (pin "B5") (pinfunction "CC2_B5") (pintype "bidirectional"))
    )
    (net (code "94") (name "PWM0") (class "Default")
      (node (ref "J18") (pin "66") (pinfunction "D4_66") (pintype "bidirectional"))
      (node (ref "J3") (pin "52") (pinfunction "52_52") (pintype "passive"))
      (node (ref "JP24") (pin "2") (pinfunction "2_2") (pintype "passive"))
    )
    (net (code "95") (name "PWM1") (class "Default")
      (node (ref "J18") (pin "68") (pinfunction "D5_68") (pintype "bidirectional"))
      (node (ref "J3") (pin "54") (pinfunction "54_54") (pintype "passive"))
      (node (ref "JP20") (pin "2") (pinfunction "2_2") (pintype "passive"))
    )
    (net (code "96") (name "PWM2") (class "Default")
      (node (ref "J18") (pin "70") (pinfunction "D6_70") (pintype "bidirectional"))
      (node (ref "J3") (pin "56") (pinfunction "56_56") (pintype "passive"))
      (node (ref "JP22") (pin "2") (pinfunction "2_2") (pintype "passive"))
    )
    (net (code "97") (name "PWM3") (class "Default")
      (node (ref "J18") (pin "72") (pinfunction "D7_72") (pintype "bidirectional"))
      (node (ref "J3") (pin "58") (pinfunction "58_58") (pintype "passive"))
      (node (ref "JP21") (pin "2") (pinfunction "2_2") (pintype "passive"))
    )
    (net (code "98") (name "REGN") (class "Default")
      (node (ref "J6") (pin "8") (pinfunction "NC_8") (pintype "passive"))
      (node (ref "J6") (pin "@8") (pinfunction "NC_@8") (pintype "passive"))
      (node (ref "J6") (pin "P$8") (pinfunction "NC_P$8") (pintype "passive"))
      (node (ref "RT1") (pin "2") (pinfunction "2_2") (pintype "bidirectional"))
      (node (ref "TP1") (pin "1") (pinfunction "1_1") (pintype "bidirectional"))
    )
    (net (code "99") (name "RTS") (class "Default")
      (node (ref "J18") (pin "42") (pinfunction "RTS_42") (pintype "bidirectional"))
      (node (ref "J3") (pin "28") (pinfunction "28_28") (pintype "passive"))
    )
    (net (code "100") (name "RX") (class "Default")
      (node (ref "J18") (pin "38") (pinfunction "RXD_38") (pintype "bidirectional"))
      (node (ref "J3") (pin "24") (pinfunction "24_24") (pintype "passive"))
      (node (ref "JP15") (pin "1") (pinfunction "1_1") (pintype "passive"))
    )
    (net (code "101") (name "SCK") (class "Default")
      (node (ref "J18") (pin "54") (pinfunction "SCLK_54") (pintype "bidirectional"))
      (node (ref "J3") (pin "40") (pinfunction "40_40") (pintype "passive"))
      (node (ref "JP12") (pin "1") (pinfunction "1_1") (pintype "passive"))
    )
    (net (code "102") (name "SCL") (class "Default")
      (node (ref "J18") (pin "20") (pinfunction "SCL_20") (pintype "bidirectional"))
      (node (ref "J3") (pin "14") (pinfunction "14_14") (pintype "passive"))
      (node (ref "J4") (pin "4") (pinfunction "4_4") (pintype "passive"))
      (node (ref "J6") (pin "14") (pinfunction "SCL_14") (pintype "passive"))
      (node (ref "J6") (pin "@14") (pinfunction "SCL_@14") (pintype "passive"))
      (node (ref "J6") (pin "P$14") (pinfunction "SCL_P$14") (pintype "passive"))
      (node (ref "JP27") (pin "2") (pinfunction "2_2") (pintype "passive"))
      (node (ref "U2") (pin "6") (pinfunction "SCL_6") (pintype "input"))
    )
    (net (code "103") (name "SDA") (class "Default")
      (node (ref "J18") (pin "22") (pinfunction "SDA_22") (pintype "bidirectional"))
      (node (ref "J3") (pin "16") (pinfunction "16_16") (pintype "passive"))
      (node (ref "J4") (pin "3") (pinfunction "3_3") (pintype "passive"))
      (node (ref "J6") (pin "15") (pinfunction "SDA_15") (pintype "passive"))
      (node (ref "J6") (pin "@15") (pinfunction "SDA_@15") (pintype "passive"))
      (node (ref "J6") (pin "P$15") (pinfunction "SDA_P$15") (pintype "passive"))
      (node (ref "JP28") (pin "2") (pinfunction "2_2") (pintype "passive"))
      (node (ref "U2") (pin "5") (pinfunction "SDA_5") (pintype "bidirectional"))
    )
    (net (code "104") (name "SOM5") (class "Default")
      (node (ref "C7") (pin "1") (pinfunction "1_1") (pintype "passive"))
      (node (ref "D7") (pin "2") (pinfunction "2_2") (pintype "bidirectional"))
      (node (ref "J13") (pin "C1") (pinfunction "VCC_C1") (pintype "passive"))
      (node (ref "J18") (pin "67") (pinfunction "SIM_VCC_67") (pintype "power_in"))
      (node (ref "J3") (pin "51") (pinfunction "51_51") (pintype "passive"))
      (node (ref "U7") (pin "8") (pinfunction "VCC_8") (pintype "power_in"))
    )
    (net (code "105") (name "SOM6") (class "Default")
      (node (ref "C4") (pin "1") (pinfunction "1_1") (pintype "passive"))
      (node (ref "D13") (pin "2") (pinfunction "2_2") (pintype "bidirectional"))
      (node (ref "J13") (pin "C2") (pinfunction "RST_C2") (pintype "passive"))
      (node (ref "J18") (pin "69") (pinfunction "SIM_RST_69") (pintype "bidirectional"))
      (node (ref "J3") (pin "53") (pinfunction "53_53") (pintype "passive"))
      (node (ref "U7") (pin "7") (pinfunction "RST_7") (pintype "bidirectional"))
    )
    (net (code "106") (name "SOM7") (class "Default")
      (node (ref "C6") (pin "1") (pinfunction "1_1") (pintype "passive"))
      (node (ref "D11") (pin "2") (pinfunction "2_2") (pintype "bidirectional"))
      (node (ref "J13") (pin "C3") (pinfunction "CLK_C3") (pintype "passive"))
      (node (ref "J18") (pin "71") (pinfunction "SIM_CLK_71") (pintype "bidirectional"))
      (node (ref "J3") (pin "55") (pinfunction "55_55") (pintype "passive"))
      (node (ref "U7") (pin "6") (pinfunction "CLK_6") (pintype "bidirectional"))
    )
    (net (code "107") (name "SOM8") (class "Default")
      (node (ref "C5") (pin "1") (pinfunction "1_1") (pintype "passive"))
      (node (ref "D12") (pin "2") (pinfunction "2_2") (pintype "bidirectional"))
      (node (ref "J13") (pin "C7") (pinfunction "I/O_C7") (pintype "passive"))
      (node (ref "J18") (pin "73") (pinfunction "SIM_DATA_73") (pintype "bidirectional"))
      (node (ref "J3") (pin "57") (pinfunction "57_57") (pintype "passive"))
      (node (ref "U7") (pin "3") (pinfunction "IO_3") (pintype "bidirectional"))
    )
    (net (code "108") (name "SOM9") (class "Default")
      (node (ref "J18") (pin "75") (pinfunction "NC_75") (pintype "bidirectional"))
      (node (ref "J3") (pin "60") (pinfunction "60_60") (pintype "passive"))
    )
    (net (code "109") (name "SOM10") (class "Default")
      (node (ref "J18") (pin "14") (pinfunction "NC_14") (pintype "bidirectional"))
      (node (ref "J3") (pin "10") (pinfunction "10_10") (pintype "passive"))
    )
    (net (code "110") (name "SOM11") (class "Default")
      (node (ref "J18") (pin "18") (pinfunction "GNSS_TXD_18") (pintype "bidirectional"))
      (node (ref "J3") (pin "12") (pinfunction "12_12") (pintype "passive"))
    )
    (net (code "111") (name "SOM12") (class "Default")
      (node (ref "J18") (pin "58") (pinfunction "D24_58") (pintype "bidirectional"))
      (node (ref "J3") (pin "44") (pinfunction "44_44") (pintype "passive"))
    )
    (net (code "112") (name "SOM13") (class "Default")
      (node (ref "J18") (pin "60") (pinfunction "D25_60") (pintype "bidirectional"))
      (node (ref "J3") (pin "46") (pinfunction "46_46") (pintype "passive"))
    )
    (net (code "113") (name "SOM14") (class "Default")
      (node (ref "J18") (pin "51") (pinfunction "NC_51") (pintype "bidirectional"))
      (node (ref "J3") (pin "35") (pinfunction "35_35") (pintype "passive"))
    )
    (net (code "114") (name "SOM15") (class "Default")
      (node (ref "J18") (pin "53") (pinfunction "SWD_CLK_53") (pintype "bidirectional"))
      (node (ref "J3") (pin "37") (pinfunction "37_37") (pintype "passive"))
    )
    (net (code "115") (name "SOM16") (class "Default")
      (node (ref "J18") (pin "55") (pinfunction "SWD_DATA_55") (pintype "bidirectional"))
      (node (ref "J3") (pin "39") (pinfunction "39_39") (pintype "passive"))
    )
    (net (code "116") (name "SOM17") (class "Default")
      (node (ref "J18") (pin "57") (pinfunction "D27_57") (pintype "bidirectional"))
      (node (ref "J3") (pin "41") (pinfunction "41_41") (pintype "bidirectional"))
    )
    (net (code "117") (name "SOM18") (class "Default")
      (node (ref "J18") (pin "59") (pinfunction "D26_59") (pintype "bidirectional"))
      (node (ref "J3") (pin "43") (pinfunction "43_43") (pintype "passive"))
    )
    (net (code "118") (name "TS") (class "Default")
      (node (ref "J21") (pin "1") (pinfunction "1_1") (pintype "bidirectional"))
      (node (ref "J6") (pin "17") (pinfunction "TS_17") (pintype "passive"))
      (node (ref "J6") (pin "@17") (pinfunction "TS_@17") (pintype "passive"))
      (node (ref "J6") (pin "P$17") (pinfunction "TS_P$17") (pintype "passive"))
      (node (ref "R23") (pin "1") (pinfunction "1_1") (pintype "passive"))
    )
    (net (code "119") (name "TX") (class "Default")
      (node (ref "J18") (pin "36") (pinfunction "TXD_36") (pintype "bidirectional"))
      (node (ref "J3") (pin "22") (pinfunction "22_22") (pintype "passive"))
      (node (ref "JP16") (pin "1") (pinfunction "1_1") (pintype "passive"))
    )
    (net (code "120") (name "UB_USB_N") (class "Default")
      (node (ref "D23") (pin "1") (pinfunction "1_1") (pintype "bidirectional"))
      (node (ref "J18") (pin "46") (pinfunction "UB_USB_N_46") (pintype "bidirectional"))
      (node (ref "USB2") (pin "A7") (pinfunction "D-_A7") (pintype "bidirectional"))
      (node (ref "USB2") (pin "B7") (pinfunction "D-_B7") (pintype "bidirectional"))
    )
    (net (code "121") (name "UB_USB_P") (class "Default")
      (node (ref "D23") (pin "4") (pinfunction "4_4") (pintype "bidirectional"))
      (node (ref "J18") (pin "44") (pinfunction "UB_USB_P_44") (pintype "bidirectional"))
      (node (ref "USB2") (pin "A6") (pinfunction "D+_A6") (pintype "bidirectional"))
      (node (ref "USB2") (pin "B6") (pinfunction "D+_B6") (pintype "bidirectional"))
    )
    (net (code "122") (name "UB_VBUS") (class "Default")
      (node (ref "D23") (pin "5") (pinfunction "5_5") (pintype "bidirectional"))
      (node (ref "F4") (pin "P$2") (pinfunction "2_P$2") (pintype "bidirectional"))
      (node (ref "USB2") (pin "VBUS1") (pinfunction "VBUS_VBUS1") (pintype "bidirectional"))
      (node (ref "USB2") (pin "VBUS2") (pinfunction "VBUS_VBUS2") (pintype "bidirectional"))
    )
    (net (code "123") (name "UB_VBUS1") (class "Default")
      (node (ref "F4") (pin "P$1") (pinfunction "1_P$1") (pintype "bidirectional"))
      (node (ref "J18") (pin "74") (pinfunction "MODEM_VBUS_74") (pintype "power_in"))
    )
    (net (code "124") (name "USB_N") (class "Default")
      (node (ref "D1") (pin "1") (pinfunction "1_1") (pintype "bidirectional"))
      (node (ref "J18") (pin "13") (pinfunction "USB_N_13") (pintype "bidirectional"))
      (node (ref "USB1") (pin "A7") (pinfunction "D-_A7") (pintype "bidirectional"))
      (node (ref "USB1") (pin "B7") (pinfunction "D-_B7") (pintype "bidirectional"))
    )
    (net (code "125") (name "USB_P") (class "Default")
      (node (ref "D1") (pin "4") (pinfunction "4_4") (pintype "bidirectional"))
      (node (ref "J18") (pin "11") (pinfunction "USB_P_11") (pintype "bidirectional"))
      (node (ref "USB1") (pin "A6") (pinfunction "D+_A6") (pintype "bidirectional"))
      (node (ref "USB1") (pin "B6") (pinfunction "D+_B6") (pintype "bidirectional"))
    )
    (net (code "126") (name "VBAT") (class "Default")
      (node (ref "J6") (pin "18") (pinfunction "VBAT_18") (pintype "passive"))
      (node (ref "J6") (pin "19") (pinfunction "VBAT_19") (pintype "passive"))
      (node (ref "J6") (pin "20") (pinfunction "VBAT_20") (pintype "passive"))
      (node (ref "J6") (pin "@18") (pinfunction "VBAT_@18") (pintype "passive"))
      (node (ref "J6") (pin "@19") (pinfunction "VBAT_@19") (pintype "passive"))
      (node (ref "J6") (pin "@20") (pinfunction "VBAT_@20") (pintype "passive"))
      (node (ref "J6") (pin "P$18") (pinfunction "VBAT_P$18") (pintype "passive"))
      (node (ref "J6") (pin "P$19") (pinfunction "VBAT_P$19") (pintype "passive"))
      (node (ref "J6") (pin "P$20") (pinfunction "VBAT_P$20") (pintype "passive"))
      (node (ref "JP17") (pin "2") (pinfunction "2_2") (pintype "passive"))
      (node (ref "Q3") (pin "3") (pinfunction "3_3") (pintype "bidirectional"))
      (node (ref "VBAT") (pin "1") (pinfunction "TP_1") (pintype "bidirectional"))
    )
    (net (code "127") (name "VBUS") (class "Default")
      (node (ref "F2") (pin "P$2") (pinfunction "2_P$2") (pintype "bidirectional"))
      (node (ref "U1") (pin "5") (pinfunction "VIN_5") (pintype "power_in"))
    )
    (net (code "128") (name "VCC") (class "Default")
      (node (ref "C10") (pin "1") (pinfunction "1_1") (pintype "passive"))
      (node (ref "C20") (pin "1") (pinfunction "1_1") (pintype "passive"))
      (node (ref "C61") (pin "1") (pinfunction "1_1") (pintype "passive"))
      (node (ref "C8") (pin "1") (pinfunction "1_1") (pintype "passive"))
      (node (ref "C9") (pin "1") (pinfunction "1_1") (pintype "passive"))
      (node (ref "D16") (pin "2") (pinfunction "P$2_2") (pintype "bidirectional"))
      (node (ref "J18") (pin "2") (pinfunction "VCC_2") (pintype "power_in"))
      (node (ref "J18") (pin "4") (pinfunction "VCC_4") (pintype "power_in"))
      (node (ref "J18") (pin "6") (pinfunction "VCC_6") (pintype "power_in"))
      (node (ref "J18") (pin "8") (pinfunction "VCC_8") (pintype "power_in"))
      (node (ref "J3") (pin "2") (pinfunction "2_2") (pintype "passive"))
      (node (ref "J3") (pin "4") (pinfunction "4_4") (pintype "passive"))
      (node (ref "J3") (pin "6") (pinfunction "6_6") (pintype "passive"))
      (node (ref "J6") (pin "5") (pinfunction "VCC_5") (pintype "passive"))
      (node (ref "J6") (pin "6") (pinfunction "VCC_6") (pintype "passive"))
      (node (ref "J6") (pin "@5") (pinfunction "VCC_@5") (pintype "passive"))
      (node (ref "J6") (pin "@6") (pinfunction "VCC_@6") (pintype "passive"))
      (node (ref "J6") (pin "P$5") (pinfunction "VCC_P$5") (pintype "passive"))
      (node (ref "J6") (pin "P$6") (pinfunction "VCC_P$6") (pintype "passive"))
      (node (ref "VCC") (pin "1") (pinfunction "TP_1") (pintype "bidirectional"))
    )
    (net (code "129") (name "VIN") (class "Default")
      (node (ref "J6") (pin "11") (pinfunction "VIN_11") (pintype "passive"))
      (node (ref "J6") (pin "12") (pinfunction "VIN_12") (pintype "passive"))
      (node (ref "J6") (pin "@11") (pinfunction "VIN_@11") (pintype "passive"))
      (node (ref "J6") (pin "@12") (pinfunction "VIN_@12") (pintype "passive"))
      (node (ref "J6") (pin "P$11") (pinfunction "VIN_P$11") (pintype "passive"))
      (node (ref "J6") (pin "P$12") (pinfunction "VIN_P$12") (pintype "passive"))
      (node (ref "Q4") (pin "3") (pinfunction "3_3") (pintype "bidirectional"))
      (node (ref "R11") (pin "2") (pinfunction "2_2") (pintype "passive"))
      (node (ref "R18") (pin "2") (pinfunction "2_2") (pintype "passive"))
      (node (ref "VIN") (pin "1") (pinfunction "TP_1") (pintype "bidirectional"))
    )
    (net (code "130") (name "VPP") (class "Default")
      (node (ref "U7") (pin "2") (pinfunction "VPP_2") (pintype "power_in"))
    )
    (net (code "131") (name "VUSB") (class "Default")
      (node (ref "D1") (pin "5") (pinfunction "5_5") (pintype "bidirectional"))
      (node (ref "F2") (pin "P$1") (pinfunction "1_P$1") (pintype "bidirectional"))
      (node (ref "USB1") (pin "VBUS1") (pinfunction "VBUS_VBUS1") (pintype "bidirectional"))
      (node (ref "USB1") (pin "VBUS2") (pinfunction "VBUS_VBUS2") (pintype "bidirectional"))
    )
    (net (code "132") (name "VUSB-MCU") (class "Default")
      (node (ref "J18") (pin "16") (pinfunction "NC_16") (pintype "power_in"))
      (node (ref "JP19") (pin "2") (pinfunction "2_2") (pintype "passive"))
      (node (ref "U1") (pin "1") (pinfunction "VOUT_1") (pintype "power_in"))
    )
    (net (code "133") (name "unconnected-(D1-Pad3)") (class "Default")
      (node (ref "D1") (pin "3") (pinfunction "3_3") (pintype "bidirectional"))
    )
    (net (code "134") (name "unconnected-(D1-Pad6)") (class "Default")
      (node (ref "D1") (pin "6") (pinfunction "6_6") (pintype "bidirectional"))
    )
    (net (code "135") (name "unconnected-(D23-Pad3)") (class "Default")
      (node (ref "D23") (pin "3") (pinfunction "3_3") (pintype "bidirectional"))
    )
    (net (code "136") (name "unconnected-(D23-Pad6)") (class "Default")
      (node (ref "D23") (pin "6") (pinfunction "6_6") (pintype "bidirectional"))
    )
    (net (code "137") (name "unconnected-(J3-Pad30)") (class "Default")
      (node (ref "J3") (pin "30") (pinfunction "30_30") (pintype "passive"))
    )
    (net (code "138") (name "unconnected-(J3-Pad32)") (class "Default")
      (node (ref "J3") (pin "32") (pinfunction "32_32") (pintype "passive"))
    )
    (net (code "139") (name "unconnected-(J11-5-PadNC1)") (class "Default")
      (node (ref "J11") (pin "NC1") (pinfunction "5_NC1") (pintype "bidirectional"))
    )
    (net (code "140") (name "unconnected-(J11-6-PadNC2)") (class "Default")
      (node (ref "J11") (pin "NC2") (pinfunction "6_NC2") (pintype "bidirectional"))
    )
    (net (code "141") (name "unconnected-(J13-VPP-PadC6)") (class "Default")
      (node (ref "J13") (pin "C6") (pinfunction "VPP_C6") (pintype "passive"))
    )
    (net (code "142") (name "unconnected-(JTAG-Pad7)") (class "Default")
      (node (ref "JTAG") (pin "7") (pinfunction "7_7") (pintype "bidirectional"))
    )
    (net (code "143") (name "unconnected-(JTAG-Pad8)") (class "Default")
      (node (ref "JTAG") (pin "8") (pinfunction "8_8") (pintype "bidirectional"))
    )
    (net (code "144") (name "unconnected-(U1-FLG-Pad3)") (class "Default")
      (node (ref "U1") (pin "3") (pinfunction "FLG_3") (pintype "bidirectional"))
    )
    (net (code "145") (name "unconnected-(U7-NA1-Pad4)") (class "Default")
      (node (ref "U7") (pin "4") (pinfunction "NA1_4") (pintype "bidirectional"))
    )
    (net (code "146") (name "unconnected-(U7-NA2-Pad5)") (class "Default")
      (node (ref "U7") (pin "5") (pinfunction "NA2_5") (pintype "bidirectional"))
    )
    (net (code "147") (name "unconnected-(X1-Pad1)") (class "Default")
      (node (ref "X1") (pin "1") (pinfunction "1_1") (pintype "passive"))
    )
    (net (code "148") (name "unconnected-(X2-Pad1)") (class "Default")
      (node (ref "X2") (pin "1") (pinfunction "1_1") (pintype "passive"))
    )
    (net (code "149") (name "unconnected-(X3-Pad1)") (class "Default")
      (node (ref "X3") (pin "1") (pinfunction "1_1") (pintype "passive"))
    )
    (net (code "150") (name "~{MODE}") (class "Default")
      (node (ref "J18") (pin "32") (pinfunction "~{MODE}_32") (pintype "bidirectional"))
      (node (ref "J3") (pin "18") (pinfunction "18_18") (pintype "passive"))
      (node (ref "MODE") (pin "3") (pinfunction "3_3") (pintype "passive"))
      (node (ref "MODE") (pin "4") (pinfunction "4_4") (pintype "passive"))
      (node (ref "R12") (pin "1") (pinfunction "1_1") (pintype "passive"))
    )
    (net (code "151") (name "~{RESET}") (class "Default")
      (node (ref "C1") (pin "1") (pinfunction "1_1") (pintype "passive"))
      (node (ref "J18") (pin "!RESET") (pinfunction "~{RESET}_!RESET") (pintype "power_in"))
      (node (ref "J18") (pin "34") (pinfunction "~{RESET}_34") (pintype "bidirectional"))
      (node (ref "J3") (pin "20") (pinfunction "20_20") (pintype "passive"))
      (node (ref "J6") (pin "23") (pinfunction "~{RST}_23") (pintype "passive"))
      (node (ref "J6") (pin "@23") (pinfunction "~{RST}_@23") (pintype "passive"))
      (node (ref "J6") (pin "P$23") (pinfunction "~{RST}_P$23") (pintype "passive"))
      (node (ref "JP5") (pin "1") (pinfunction "1_1") (pintype "passive"))
      (node (ref "JTAG") (pin "10") (pinfunction "10_10") (pintype "bidirectional"))
      (node (ref "R4") (pin "1") (pinfunction "1_1") (pintype "passive"))
      (node (ref "RESET") (pin "3") (pinfunction "3_3") (pintype "passive"))
      (node (ref "RESET") (pin "4") (pinfunction "4_4") (pintype "passive"))
    )
  )
)
